# chipKIT_Max32.net
KiCad netlist of a schematic drawn in EAGLE
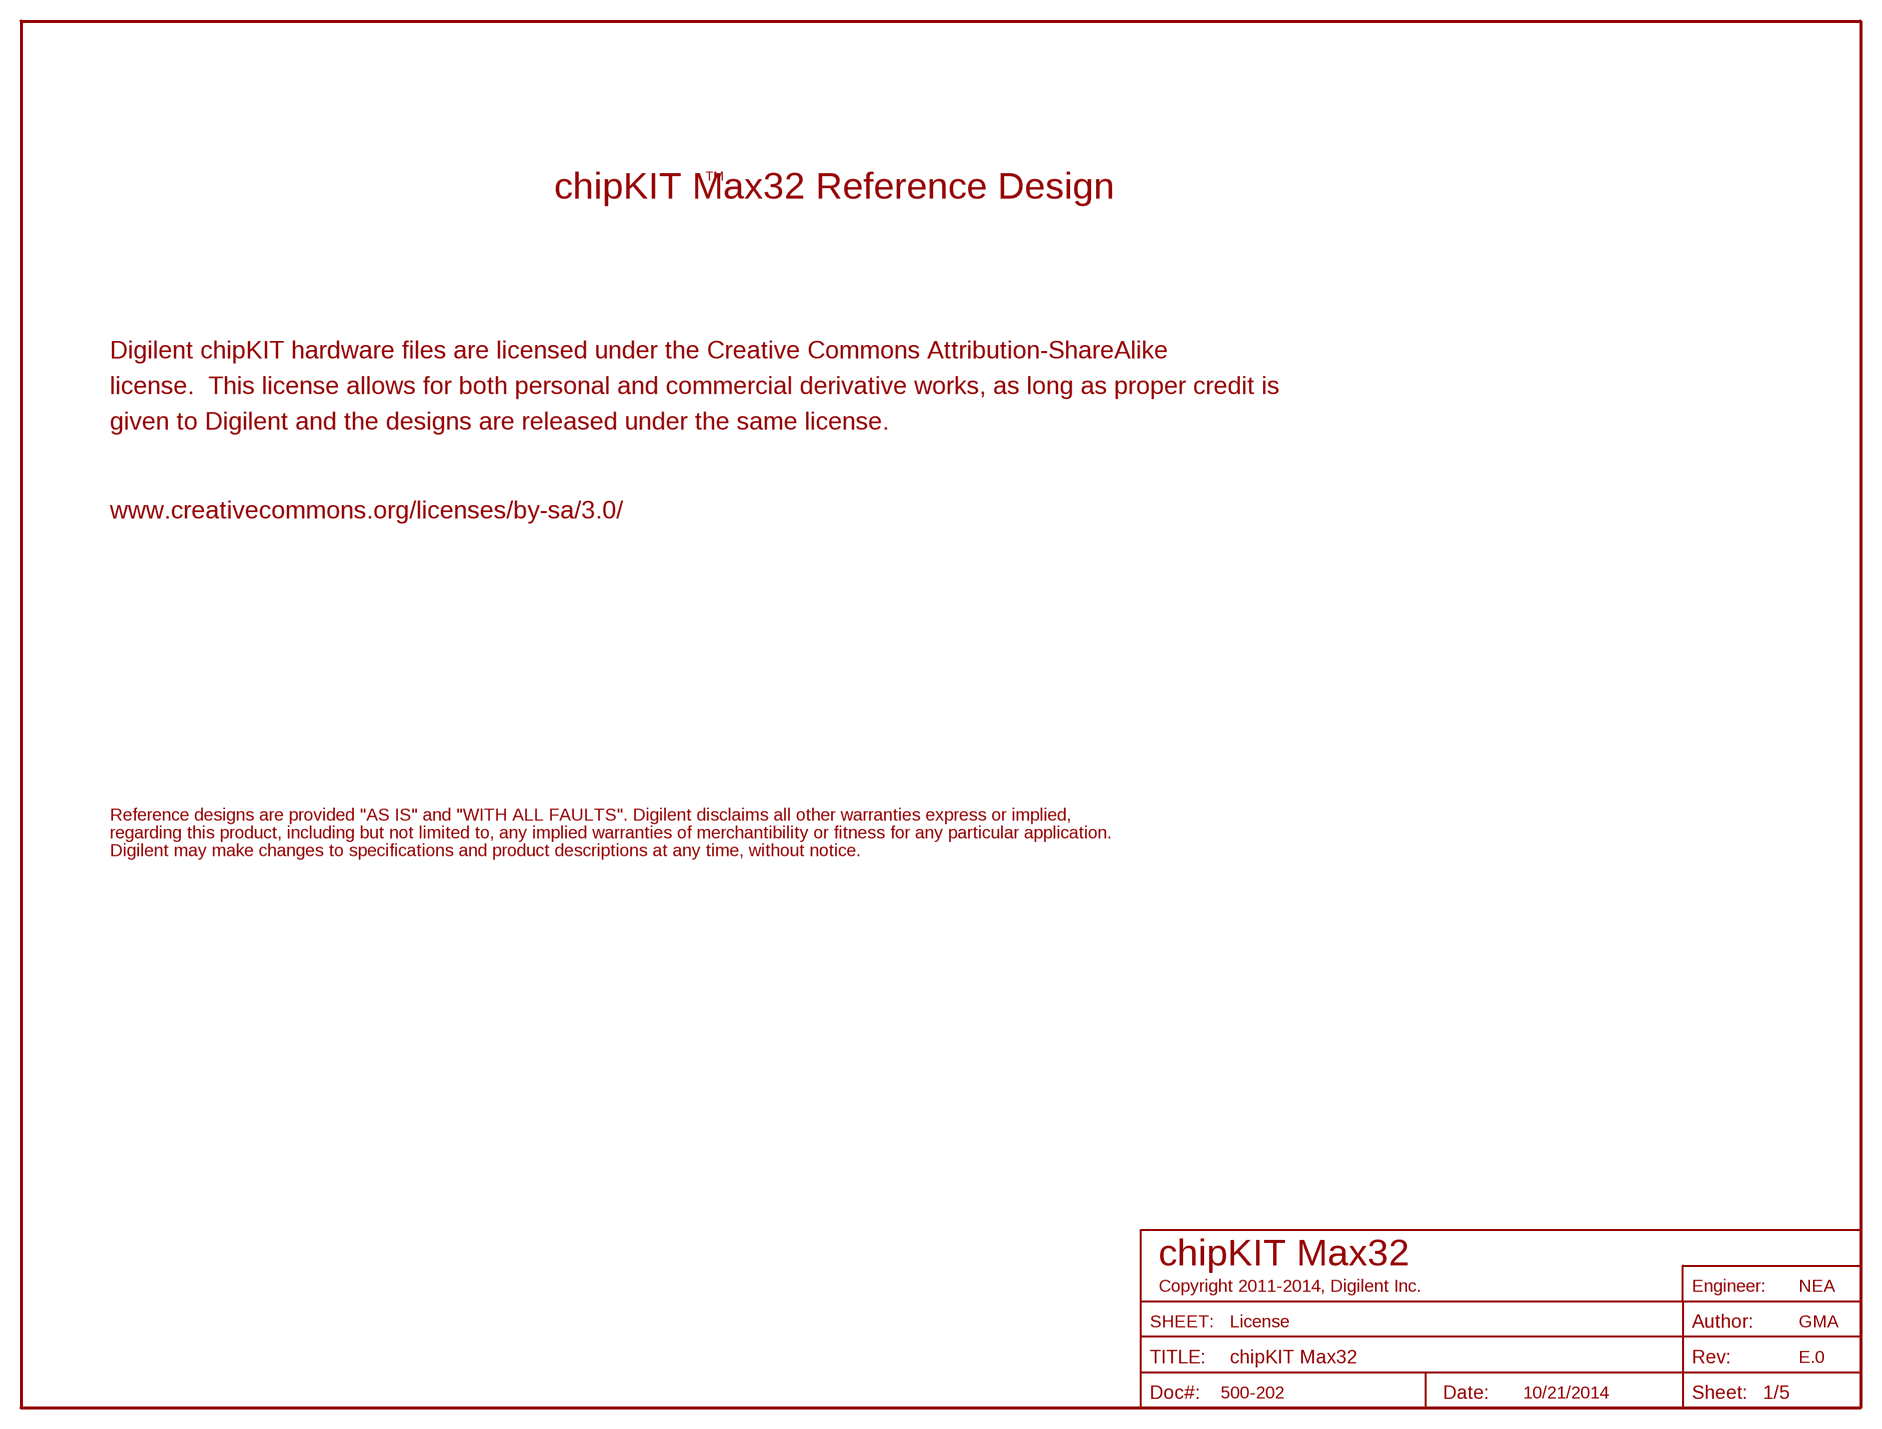
[diagram p0: schematic, sheet 1]
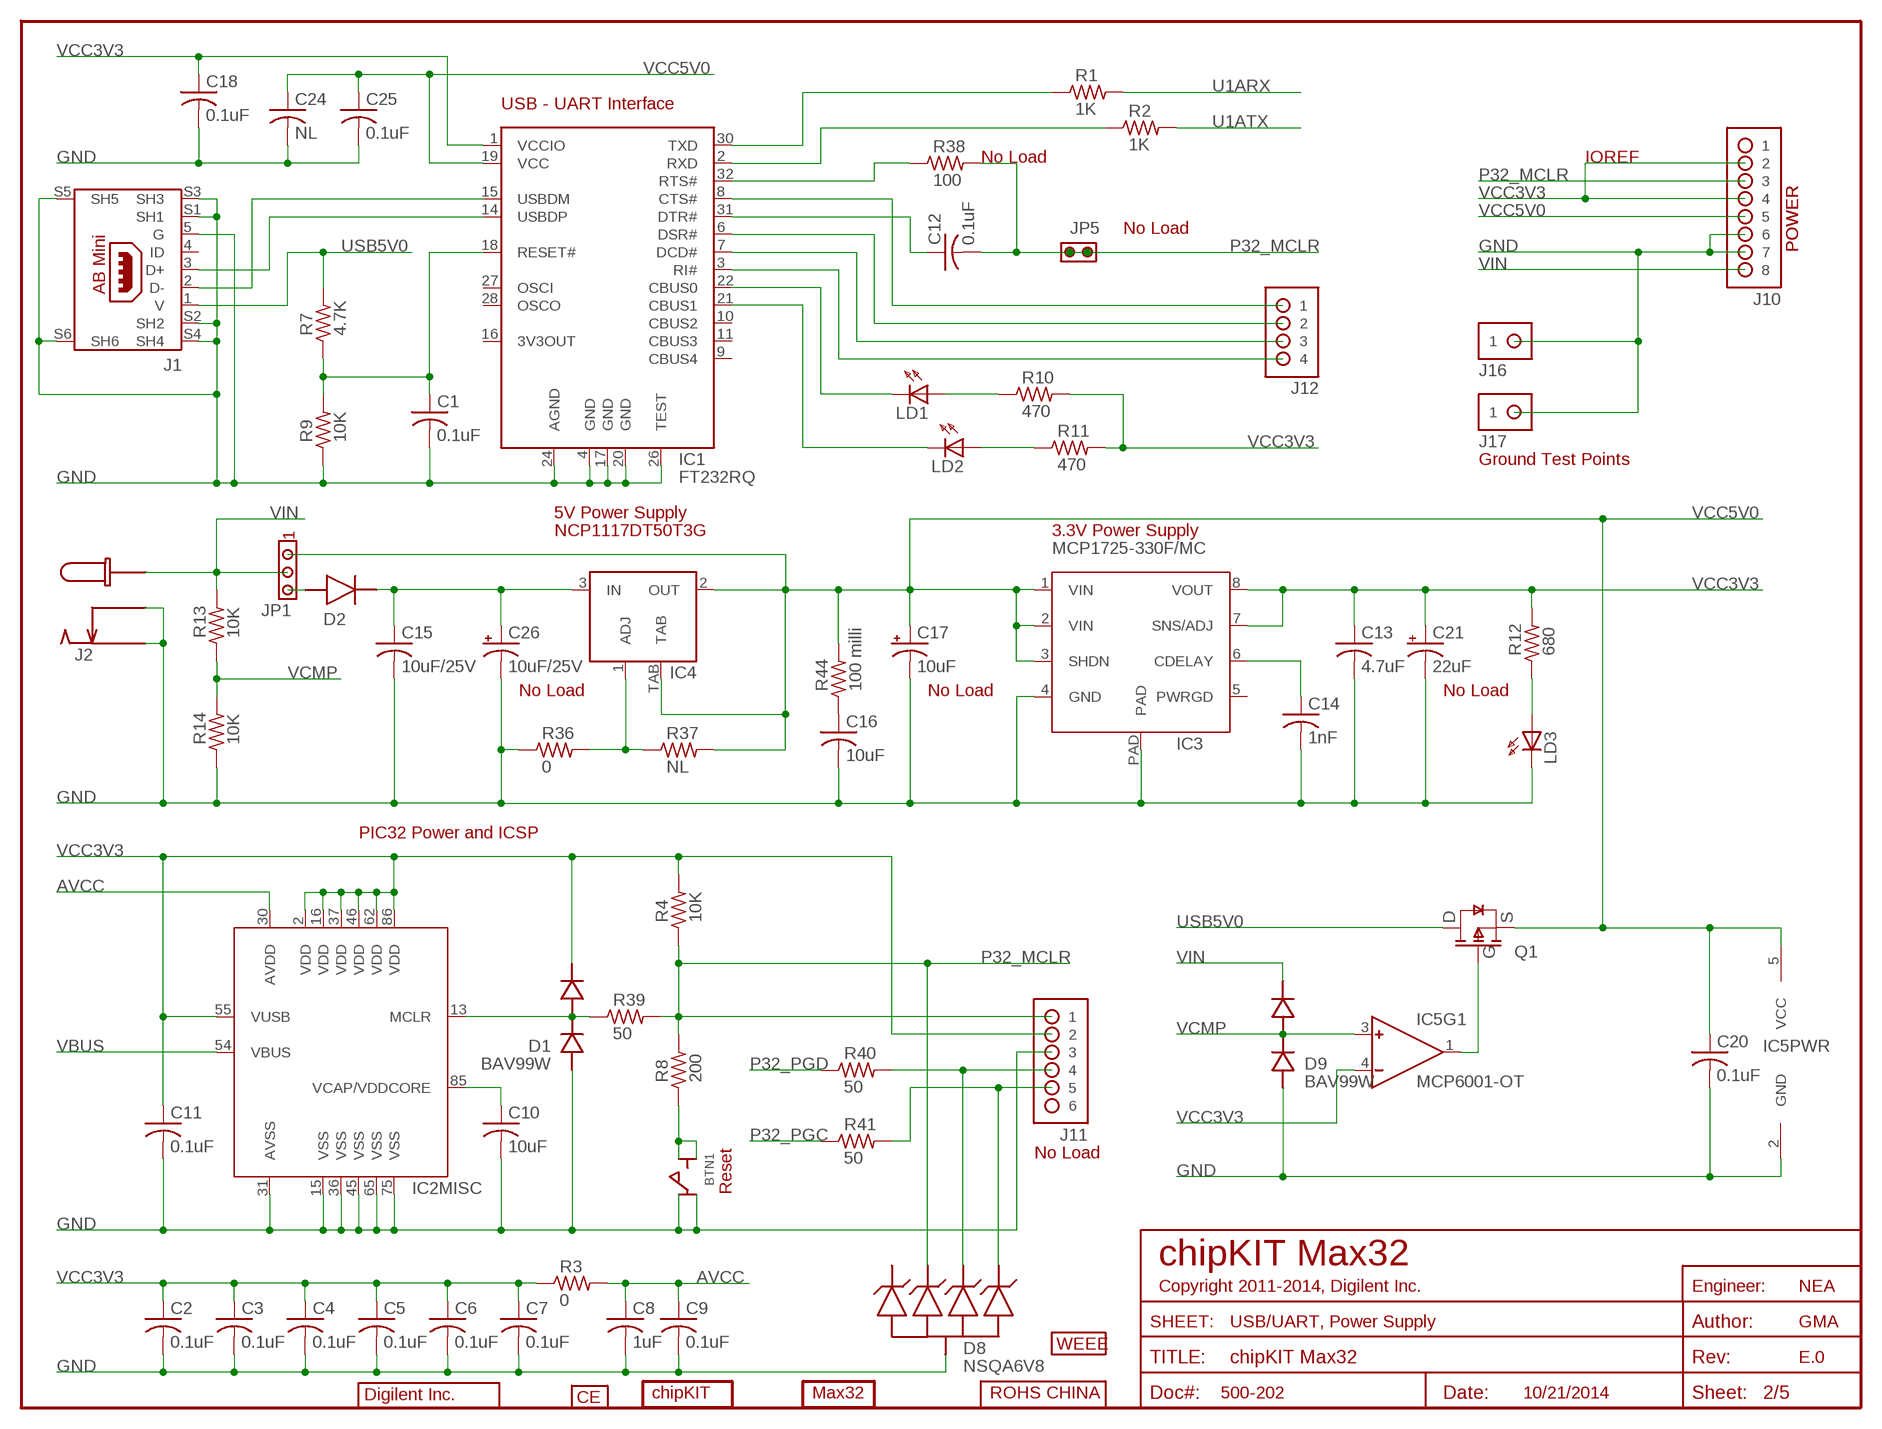
[diagram p1: schematic, sheet 2]
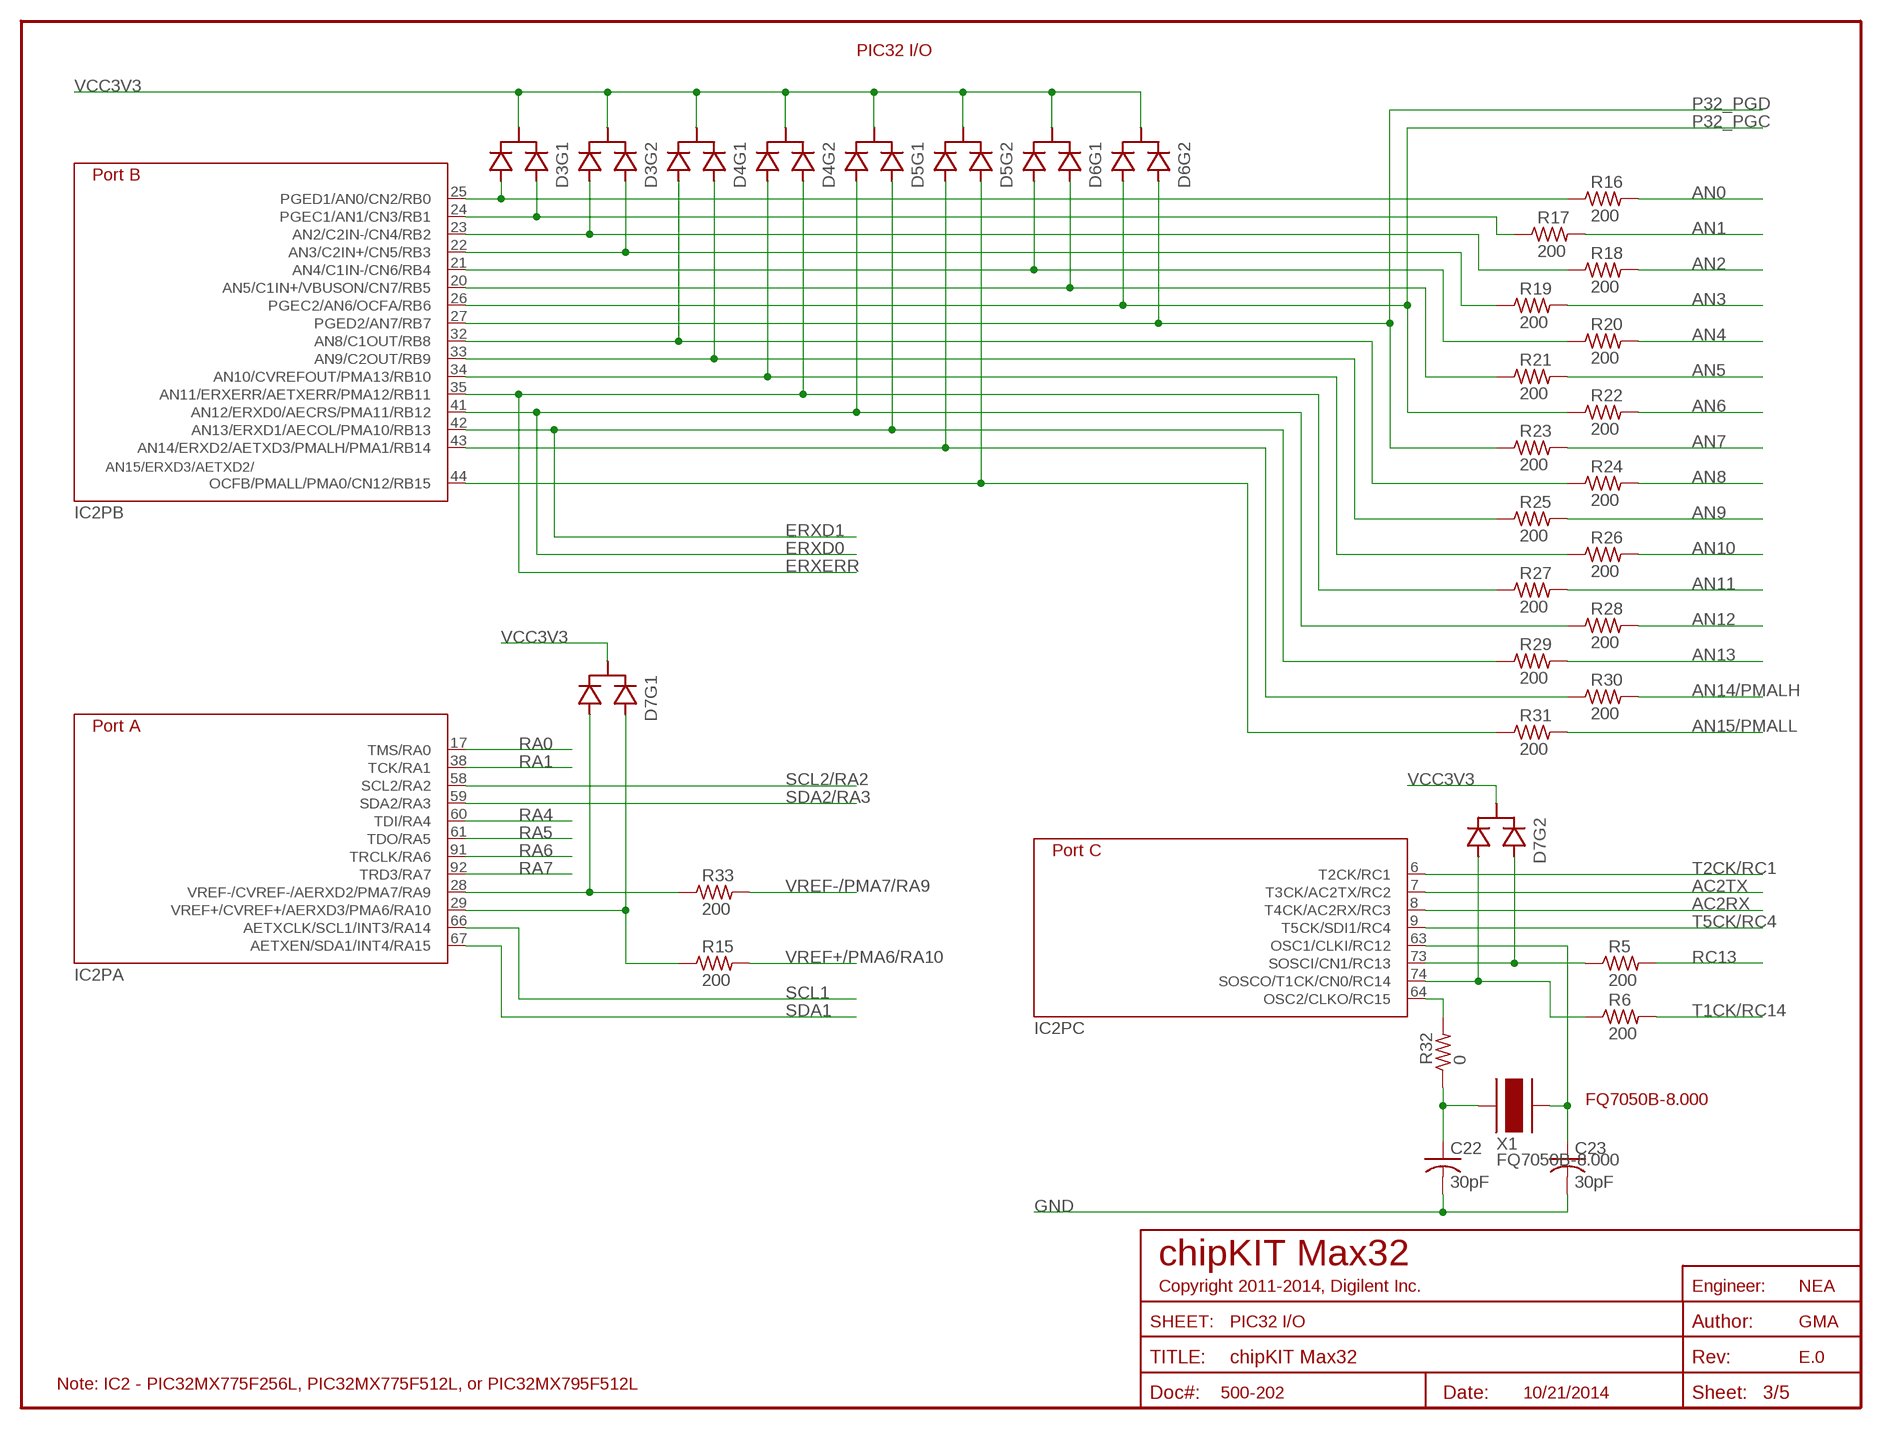
[diagram p2: schematic, sheet 3]
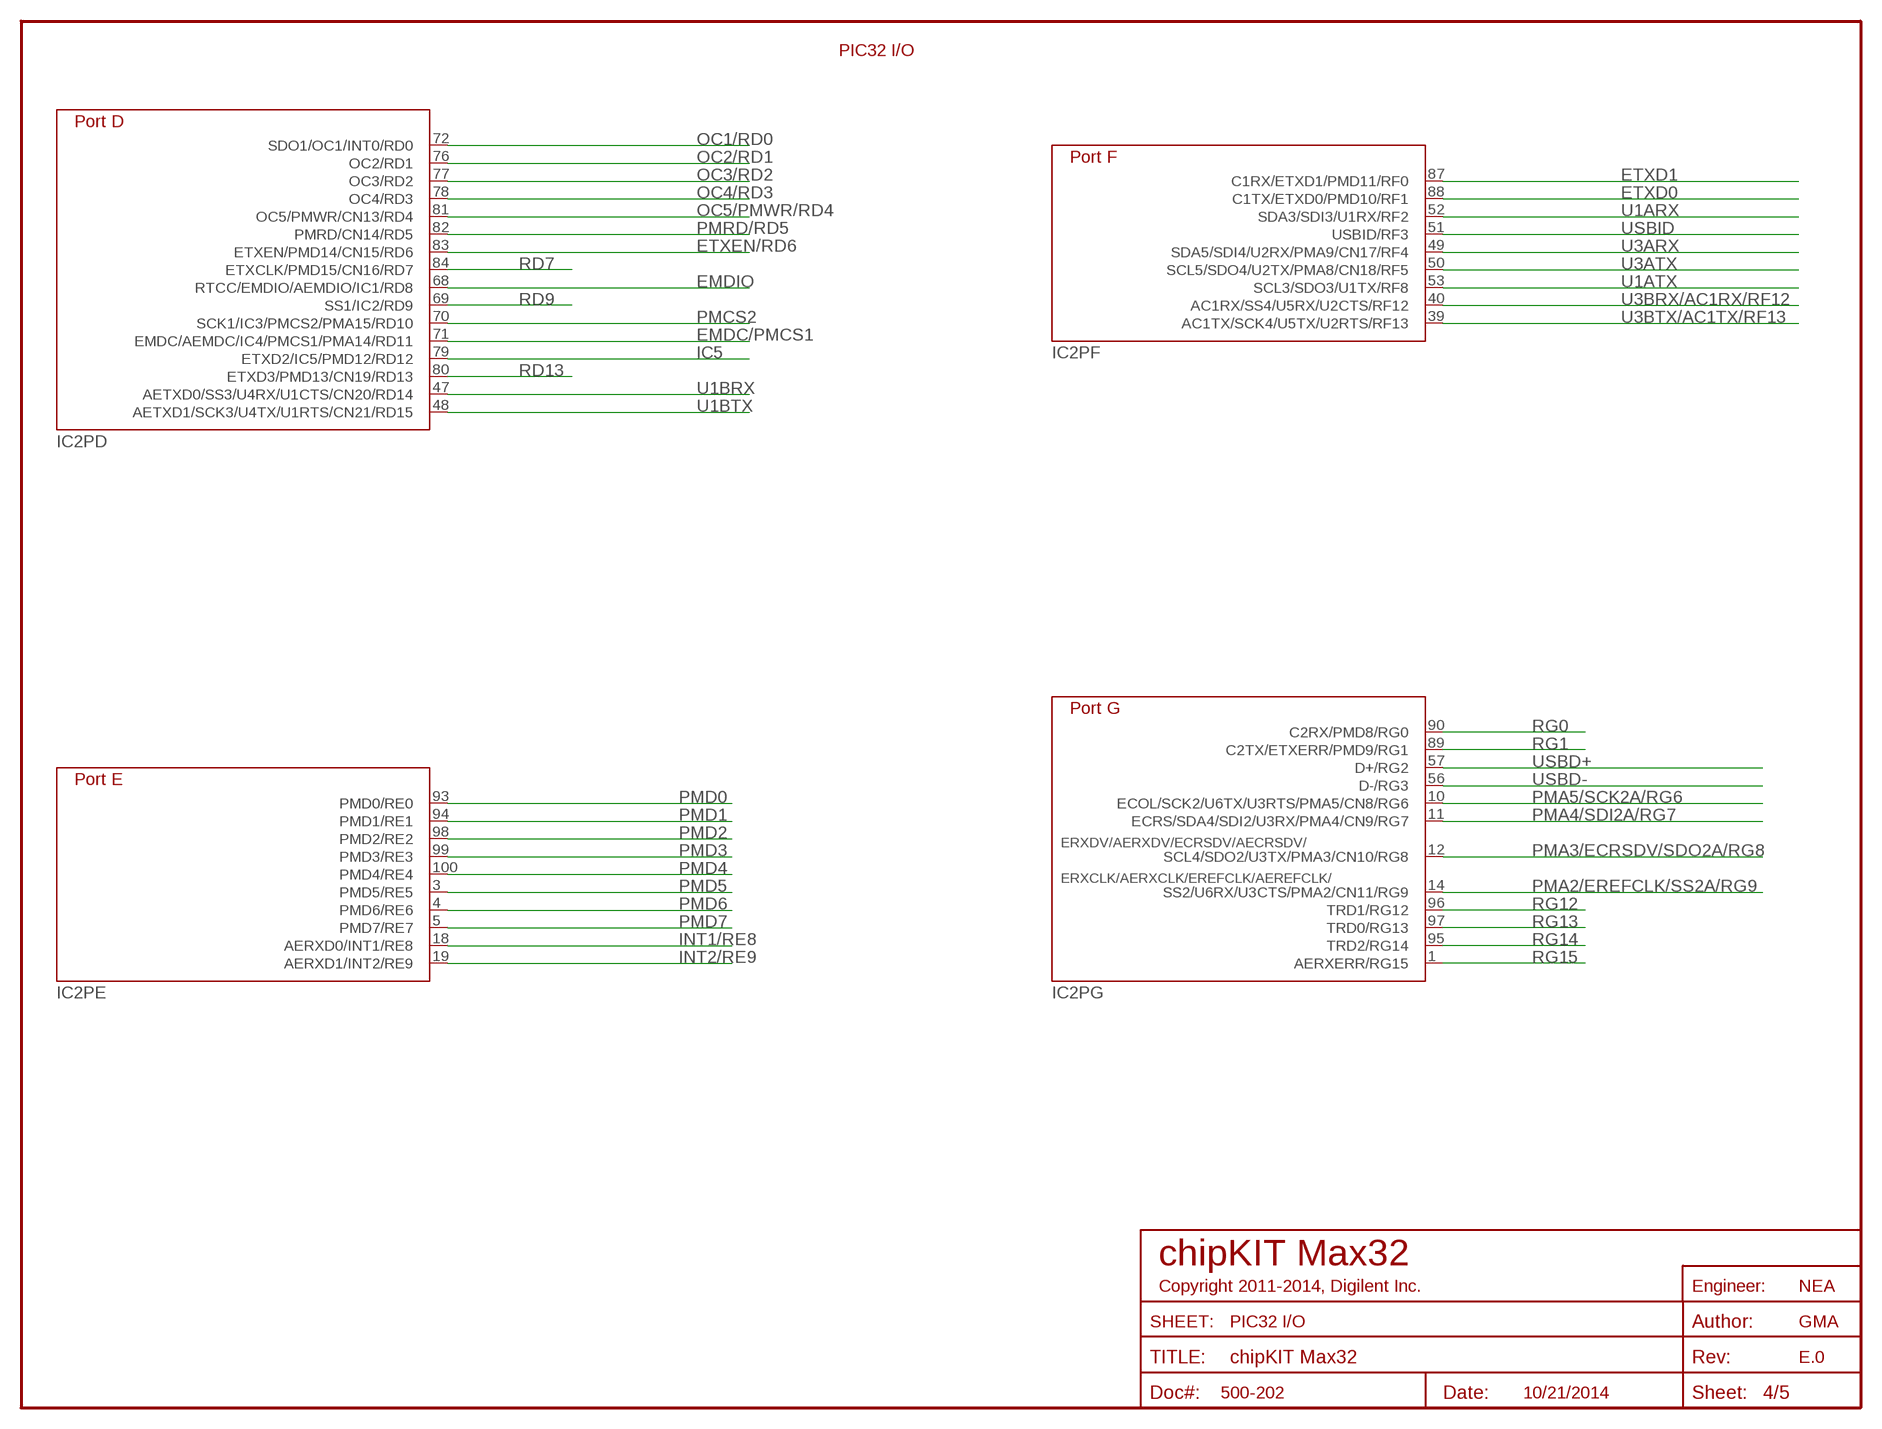
[diagram p3: schematic, sheet 4]
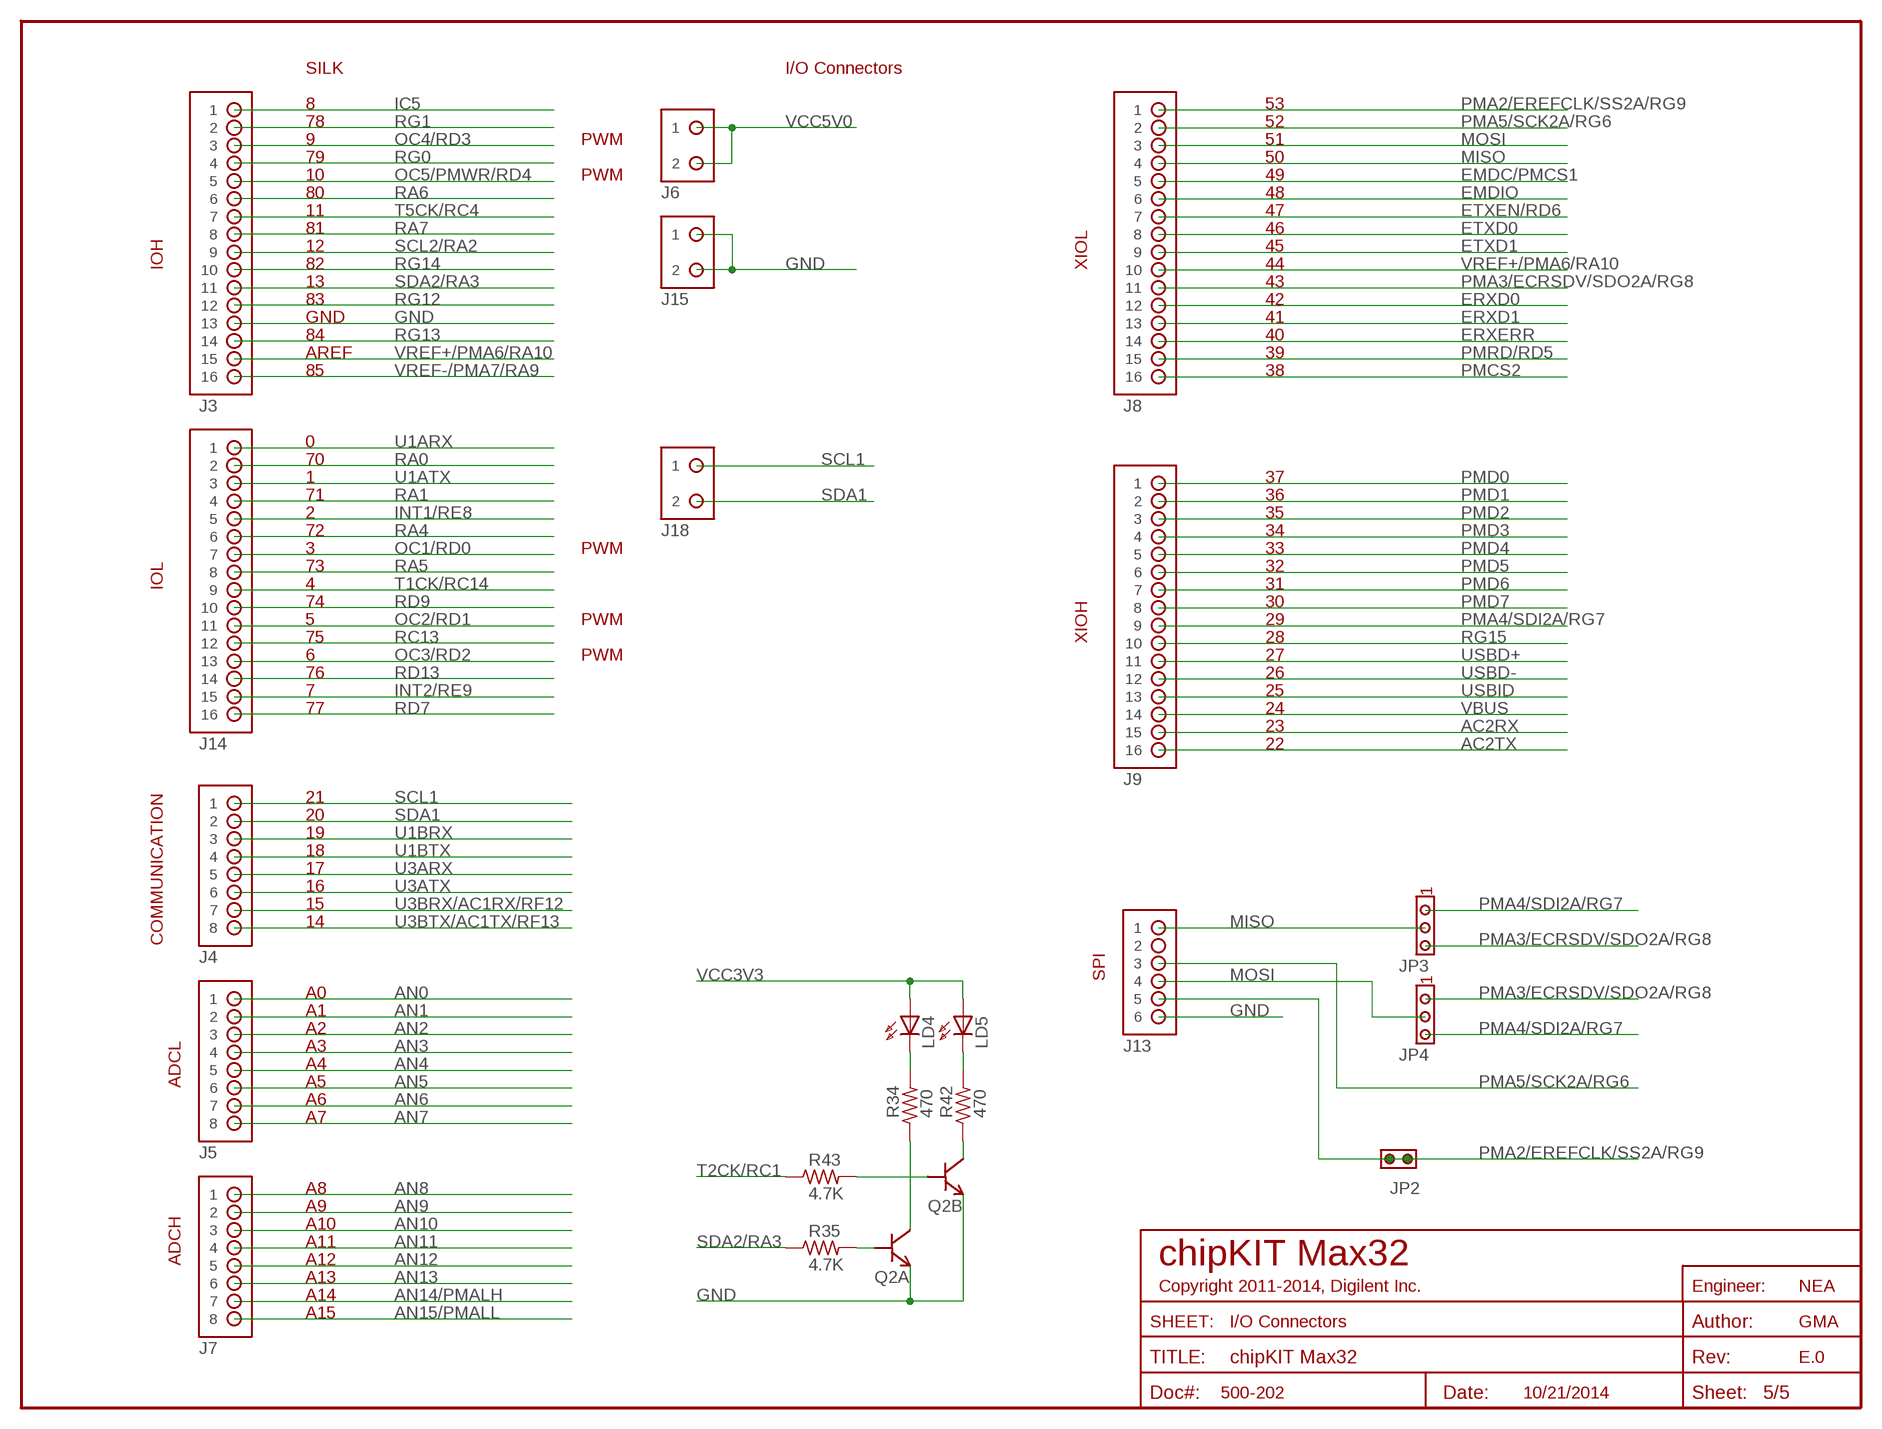
[diagram p4: schematic, sheet 5]

(export (version "E")
  (design (tool "Eeschema 10.0.6"))
  (components
    (comp (ref "BTN1")
      (value "SW-P8008")
      (footprint "eagle-import:SW-P8008")
      (libsource (lib "eagle-import") (part "SW-P8008"))
    )
    (comp (ref "C1")
      (value "0.1uF")
      (footprint "eagle-import:C0402S")
      (libsource (lib "eagle-import") (part "CAP-S0402S"))
    )
    (comp (ref "C2")
      (value "0.1uF")
      (footprint "eagle-import:C0402S")
      (libsource (lib "eagle-import") (part "CAP-S0402S"))
    )
    (comp (ref "C3")
      (value "0.1uF")
      (footprint "eagle-import:C0402S")
      (libsource (lib "eagle-import") (part "CAP-S0402S"))
    )
    (comp (ref "C4")
      (value "0.1uF")
      (footprint "eagle-import:C0402S")
      (libsource (lib "eagle-import") (part "CAP-S0402S"))
    )
    (comp (ref "C5")
      (value "0.1uF")
      (footprint "eagle-import:C0402S")
      (libsource (lib "eagle-import") (part "CAP-S0402S"))
    )
    (comp (ref "C6")
      (value "0.1uF")
      (footprint "eagle-import:C0402S")
      (libsource (lib "eagle-import") (part "CAP-S0402S"))
    )
    (comp (ref "C7")
      (value "0.1uF")
      (footprint "eagle-import:C0402S")
      (libsource (lib "eagle-import") (part "CAP-S0402S"))
    )
    (comp (ref "C8")
      (value "1uF")
      (footprint "eagle-import:C0402S")
      (libsource (lib "eagle-import") (part "CAP-S0402S"))
    )
    (comp (ref "C9")
      (value "0.1uF")
      (footprint "eagle-import:C0402S")
      (libsource (lib "eagle-import") (part "CAP-S0402S"))
    )
    (comp (ref "C10")
      (value "10uF")
      (footprint "eagle-import:C0603S")
      (libsource (lib "eagle-import") (part "CAP-S0603S"))
    )
    (comp (ref "C11")
      (value "0.1uF")
      (footprint "eagle-import:C0402S")
      (libsource (lib "eagle-import") (part "CAP-S0402S"))
    )
    (comp (ref "C12")
      (value "0.1uF")
      (footprint "eagle-import:C0402S")
      (libsource (lib "eagle-import") (part "CAP-S0402S"))
    )
    (comp (ref "C13")
      (value "4.7uF")
      (footprint "eagle-import:C0603S")
      (libsource (lib "eagle-import") (part "CAP-S0603S"))
    )
    (comp (ref "C14")
      (value "1nF")
      (footprint "eagle-import:C0402S")
      (libsource (lib "eagle-import") (part "CAP-S0402S"))
    )
    (comp (ref "C15")
      (value "10uF/25V")
      (footprint "eagle-import:C0805S")
      (libsource (lib "eagle-import") (part "CAP-S0805S"))
    )
    (comp (ref "C16")
      (value "10uF")
      (footprint "eagle-import:C0603S")
      (libsource (lib "eagle-import") (part "CAP-S0603S"))
    )
    (comp (ref "C17")
      (value "10uF")
      (footprint "eagle-import:CPOL3216")
      (libsource (lib "eagle-import") (part "CPOL-SA"))
    )
    (comp (ref "C18")
      (value "0.1uF")
      (footprint "eagle-import:C0402S")
      (libsource (lib "eagle-import") (part "CAP-S0402S"))
    )
    (comp (ref "C20")
      (value "0.1uF")
      (footprint "eagle-import:C0402")
      (libsource (lib "eagle-import") (part "CAP-S0402"))
    )
    (comp (ref "C21")
      (value "22uF")
      (footprint "eagle-import:CPOL3216")
      (libsource (lib "eagle-import") (part "CPOL-SA"))
    )
    (comp (ref "C24")
      (value "NL")
      (footprint "eagle-import:C0603S")
      (libsource (lib "eagle-import") (part "CAP-S0603S"))
    )
    (comp (ref "C25")
      (value "0.1uF")
      (footprint "eagle-import:C0402S")
      (libsource (lib "eagle-import") (part "CAP-S0402S"))
    )
    (comp (ref "C26")
      (value "10uF/25V")
      (footprint "eagle-import:CPOL3216")
      (libsource (lib "eagle-import") (part "CPOL-SA"))
    )
    (comp (ref "D1")
      (value "BAV99W")
      (footprint "eagle-import:SOT-323")
      (libsource (lib "eagle-import") (part "BAV99W"))
    )
    (comp (ref "D2")
      (value "B220A")
      (footprint "eagle-import:SMA")
      (libsource (lib "eagle-import") (part "DIODESMA"))
    )
    (comp (ref "D8")
      (value "NSQA6V8")
      (footprint "eagle-import:SOT-323-5")
      (libsource (lib "eagle-import") (part "NSQA6V8"))
    )
    (comp (ref "D9")
      (value "BAV99W")
      (footprint "eagle-import:SOT-323")
      (libsource (lib "eagle-import") (part "BAV99W"))
    )
    (comp (ref "IC1")
      (value "FT232RQ")
      (footprint "eagle-import:QFN32")
      (libsource (lib "eagle-import") (part "FT232RQ"))
    )
    (comp (ref "IC2")
      (value "PIC32MX7X5FL-PT")
      (footprint "eagle-import:TQ100-PT")
      (libsource (lib "eagle-import") (part "PIC32MX7X5FL-PT"))
    )
    (comp (ref "IC3")
      (value "MCP1725-330F/MC")
      (footprint "eagle-import:DFN8-MC")
      (libsource (lib "eagle-import") (part "MCP1725MC"))
    )
    (comp (ref "IC4")
      (value "NCP1117DT50T3G")
      (footprint "eagle-import:SOT223")
      (libsource (lib "eagle-import") (part "LM1117MP"))
    )
    (comp (ref "IC5")
      (value "MCP6001-OT")
      (footprint "eagle-import:SOT23-5-OT")
      (libsource (lib "eagle-import") (part "MCP6001-OT"))
    )
    (comp (ref "J1")
      (value "USB-AB-MINI")
      (footprint "eagle-import:USB-AB-MINI")
      (libsource (lib "eagle-import") (part "USB-AB-MINI"))
    )
    (comp (ref "J2")
      (value "CON-COAX-KLD0202-S")
      (footprint "eagle-import:KLD-0202S")
      (libsource (lib "eagle-import") (part "CON-COAX-KLD0202-S"))
    )
    (comp (ref "J10")
      (value "ST Female")
      (footprint "eagle-import:HDR-1X8")
      (libsource (lib "eagle-import") (part "HDR-1X8"))
    )
    (comp (ref "J11")
      (value "No Load")
      (footprint "eagle-import:HDR-1X6_OFFSET")
      (libsource (lib "eagle-import") (part "HDR-1X6-OFFSET"))
    )
    (comp (ref "J12")
      (value "HDR-1X4")
      (footprint "eagle-import:HDR-1X4")
      (libsource (lib "eagle-import") (part "HDR-1X4"))
    )
    (comp (ref "J16")
      (value "HDR-1X1")
      (footprint "eagle-import:HDR-1X1")
      (libsource (lib "eagle-import") (part "HDR-1X1"))
    )
    (comp (ref "J17")
      (value "HDR-1X1")
      (footprint "eagle-import:HDR-1X1")
      (libsource (lib "eagle-import") (part "HDR-1X1"))
    )
    (comp (ref "JP1")
      (value "JPR-1X3")
      (footprint "eagle-import:JPR-1X3")
      (libsource (lib "eagle-import") (part "JPR-1X3"))
    )
    (comp (ref "JP5")
      (value "No Load")
      (footprint "eagle-import:JPR-1X2")
      (libsource (lib "eagle-import") (part "JPR-1X2"))
    )
    (comp (ref "LD1")
      (value "LED-S0603-RED")
      (footprint "eagle-import:D0603")
      (libsource (lib "eagle-import") (part "LED-S0603"))
    )
    (comp (ref "LD2")
      (value "LED-S0603-RED")
      (footprint "eagle-import:D0603")
      (libsource (lib "eagle-import") (part "LED-S0603"))
    )
    (comp (ref "LD3")
      (value "LED-S0603-RED")
      (footprint "eagle-import:D0603")
      (libsource (lib "eagle-import") (part "LED-S0603"))
    )
    (comp (ref "LOGO1")
      (value "ROHS-CHINA-INV")
      (footprint "eagle-import:ROHS_CHINA_INV_LOGO")
      (libsource (lib "eagle-import") (part "ROHS-CHINA-INV"))
    )
    (comp (ref "LOGO2")
      (value "WEEE-L")
      (footprint "eagle-import:WEEE_LOGO2")
      (libsource (lib "eagle-import") (part "WEEE-L"))
    )
    (comp (ref "LOGO4")
      (value "MAX32_LOGO")
      (footprint "eagle-import:MAX32_LOGO")
      (libsource (lib "eagle-import") (part "MAX32_LOGO"))
    )
    (comp (ref "LOGO5")
      (value "CHIPKIT")
      (footprint "eagle-import:CHIPKIT_LOGO")
      (libsource (lib "eagle-import") (part "CHIPKIT"))
    )
    (comp (ref "LOGO6")
      (value "CE")
      (footprint "eagle-import:CE_LOGO")
      (libsource (lib "eagle-import") (part "CE"))
    )
    (comp (ref "LOGO7")
      (value "DIGILENT_INC-BT-1500")
      (footprint "eagle-import:DIGILENT_BEYOND_1500_LOGO")
      (libsource (lib "eagle-import") (part "DIGILENT_INC-BT-1500"))
    )
    (comp (ref "Q1")
      (value "FDN340P")
      (footprint "eagle-import:SOT23")
      (libsource (lib "eagle-import") (part "FDN340P"))
    )
    (comp (ref "R1")
      (value "1K")
      (footprint "eagle-import:R0402S")
      (libsource (lib "eagle-import") (part "RES-S0402S"))
    )
    (comp (ref "R2")
      (value "1K")
      (footprint "eagle-import:R0402S")
      (libsource (lib "eagle-import") (part "RES-S0402S"))
    )
    (comp (ref "R3")
      (value "0")
      (footprint "eagle-import:R0603")
      (libsource (lib "eagle-import") (part "RES-S0603"))
    )
    (comp (ref "R4")
      (value "10K")
      (footprint "eagle-import:R0402S")
      (libsource (lib "eagle-import") (part "RES-S0402S"))
    )
    (comp (ref "R7")
      (value "4.7K")
      (footprint "eagle-import:R0402S")
      (libsource (lib "eagle-import") (part "RES-S0402S"))
    )
    (comp (ref "R8")
      (value "200")
      (footprint "eagle-import:R0402S")
      (libsource (lib "eagle-import") (part "RES-S0402S"))
    )
    (comp (ref "R9")
      (value "10K")
      (footprint "eagle-import:R0402S")
      (libsource (lib "eagle-import") (part "RES-S0402S"))
    )
    (comp (ref "R10")
      (value "470")
      (footprint "eagle-import:R0402S")
      (libsource (lib "eagle-import") (part "RES-S0402S"))
    )
    (comp (ref "R11")
      (value "470")
      (footprint "eagle-import:R0402S")
      (libsource (lib "eagle-import") (part "RES-S0402S"))
    )
    (comp (ref "R12")
      (value "680")
      (footprint "eagle-import:R0402S")
      (libsource (lib "eagle-import") (part "RES-S0402S"))
    )
    (comp (ref "R13")
      (value "10K")
      (footprint "eagle-import:R0402S")
      (libsource (lib "eagle-import") (part "RES-S0402S"))
    )
    (comp (ref "R14")
      (value "10K")
      (footprint "eagle-import:R0402S")
      (libsource (lib "eagle-import") (part "RES-S0402S"))
    )
    (comp (ref "R36")
      (value "0")
      (footprint "eagle-import:R0402S")
      (libsource (lib "eagle-import") (part "RES-S0402S"))
    )
    (comp (ref "R37")
      (value "NL")
      (footprint "eagle-import:R0402S")
      (libsource (lib "eagle-import") (part "RES-S0402S"))
    )
    (comp (ref "R38")
      (value "100")
      (footprint "eagle-import:R0402S")
      (libsource (lib "eagle-import") (part "RES-S0402S"))
    )
    (comp (ref "R39")
      (value "50")
      (footprint "eagle-import:R0402S")
      (libsource (lib "eagle-import") (part "RES-S0402S"))
    )
    (comp (ref "R40")
      (value "50")
      (footprint "eagle-import:R0402S")
      (libsource (lib "eagle-import") (part "RES-S0402S"))
    )
    (comp (ref "R41")
      (value "50")
      (footprint "eagle-import:R0402S")
      (libsource (lib "eagle-import") (part "RES-S0402S"))
    )
    (comp (ref "R44")
      (value "100 milli")
      (footprint "eagle-import:R0603S")
      (libsource (lib "eagle-import") (part "RES-S0603S"))
    )
    (comp (ref "J3")
      (value "HDR-2X8")
      (footprint "eagle-import:HDR-2X8")
      (libsource (lib "eagle-import") (part "HDR-2X8"))
    )
    (comp (ref "J4")
      (value "HDR-1X8")
      (footprint "eagle-import:HDR-1X8")
      (libsource (lib "eagle-import") (part "HDR-1X8"))
    )
    (comp (ref "J5")
      (value "HDR-1X8")
      (footprint "eagle-import:HDR-1X8")
      (libsource (lib "eagle-import") (part "HDR-1X8"))
    )
    (comp (ref "J6")
      (value "HDR-1X2")
      (footprint "eagle-import:HDR-1X2")
      (libsource (lib "eagle-import") (part "HDR-1X2"))
    )
    (comp (ref "J7")
      (value "HDR-1X8")
      (footprint "eagle-import:HDR-1X8")
      (libsource (lib "eagle-import") (part "HDR-1X8"))
    )
    (comp (ref "J8")
      (value "HDR-2X8")
      (footprint "eagle-import:HDR-2X8")
      (libsource (lib "eagle-import") (part "HDR-2X8"))
    )
    (comp (ref "J9")
      (value "HDR-2X8")
      (footprint "eagle-import:HDR-2X8")
      (libsource (lib "eagle-import") (part "HDR-2X8"))
    )
    (comp (ref "J13")
      (value "HDR-2X3")
      (footprint "eagle-import:HDR-2X3")
      (libsource (lib "eagle-import") (part "HDR-2X3"))
    )
    (comp (ref "J14")
      (value "HDR-2X8")
      (footprint "eagle-import:HDR-2X8")
      (libsource (lib "eagle-import") (part "HDR-2X8"))
    )
    (comp (ref "J15")
      (value "HDR-1X2")
      (footprint "eagle-import:HDR-1X2")
      (libsource (lib "eagle-import") (part "HDR-1X2"))
    )
    (comp (ref "J18")
      (value "ST FEMALE")
      (footprint "eagle-import:HDR-1X2")
      (libsource (lib "eagle-import") (part "HDR-1X2"))
    )
    (comp (ref "JP2")
      (value "JPR-1X2")
      (footprint "eagle-import:JPR-1X2")
      (libsource (lib "eagle-import") (part "JPR-1X2"))
    )
    (comp (ref "JP3")
      (value "JPR-1X3")
      (footprint "eagle-import:JPR-1X3")
      (libsource (lib "eagle-import") (part "JPR-1X3"))
    )
    (comp (ref "JP4")
      (value "JPR-1X3")
      (footprint "eagle-import:JPR-1X3")
      (libsource (lib "eagle-import") (part "JPR-1X3"))
    )
    (comp (ref "LD4")
      (value "LED-S0603-GRN")
      (footprint "eagle-import:D0603")
      (libsource (lib "eagle-import") (part "LED-S0603"))
    )
    (comp (ref "LD5")
      (value "LED-S0603")
      (footprint "eagle-import:D0603")
      (libsource (lib "eagle-import") (part "LED-S0603"))
    )
    (comp (ref "Q2")
      (value "MBT3904DW1T1")
      (footprint "eagle-import:SOT-363")
      (libsource (lib "eagle-import") (part "MBT3904DW1T1"))
    )
    (comp (ref "R34")
      (value "470")
      (footprint "eagle-import:R0402S")
      (libsource (lib "eagle-import") (part "RES-S0402S"))
    )
    (comp (ref "R35")
      (value "4.7K")
      (footprint "eagle-import:R0402S")
      (libsource (lib "eagle-import") (part "RES-S0402S"))
    )
    (comp (ref "R42")
      (value "470")
      (footprint "eagle-import:R0402S")
      (libsource (lib "eagle-import") (part "RES-S0402S"))
    )
    (comp (ref "R43")
      (value "4.7K")
      (footprint "eagle-import:R0402S")
      (libsource (lib "eagle-import") (part "RES-S0402S"))
    )
    (comp (ref "C22")
      (value "30pF")
      (footprint "eagle-import:C0402S")
      (libsource (lib "eagle-import") (part "CAP-S0402S"))
    )
    (comp (ref "C23")
      (value "30pF")
      (footprint "eagle-import:C0402S")
      (libsource (lib "eagle-import") (part "CAP-S0402S"))
    )
    (comp (ref "D3")
      (value "BAV70S")
      (footprint "eagle-import:SOT-363")
      (libsource (lib "eagle-import") (part "BAV70S"))
    )
    (comp (ref "D4")
      (value "BAV70S")
      (footprint "eagle-import:SOT-363")
      (libsource (lib "eagle-import") (part "BAV70S"))
    )
    (comp (ref "D5")
      (value "BAV70S")
      (footprint "eagle-import:SOT-363")
      (libsource (lib "eagle-import") (part "BAV70S"))
    )
    (comp (ref "D6")
      (value "BAV70S")
      (footprint "eagle-import:SOT-363")
      (libsource (lib "eagle-import") (part "BAV70S"))
    )
    (comp (ref "D7")
      (value "BAV70S")
      (footprint "eagle-import:SOT-363")
      (libsource (lib "eagle-import") (part "BAV70S"))
    )
    (comp (ref "R5")
      (value "200")
      (footprint "eagle-import:R0402S")
      (libsource (lib "eagle-import") (part "RES-S0402S"))
    )
    (comp (ref "R6")
      (value "200")
      (footprint "eagle-import:R0402S")
      (libsource (lib "eagle-import") (part "RES-S0402S"))
    )
    (comp (ref "R15")
      (value "200")
      (footprint "eagle-import:R0402S")
      (libsource (lib "eagle-import") (part "RES-S0402S"))
    )
    (comp (ref "R16")
      (value "200")
      (footprint "eagle-import:R0402S")
      (libsource (lib "eagle-import") (part "RES-S0402S"))
    )
    (comp (ref "R17")
      (value "200")
      (footprint "eagle-import:R0402S")
      (libsource (lib "eagle-import") (part "RES-S0402S"))
    )
    (comp (ref "R18")
      (value "200")
      (footprint "eagle-import:R0402S")
      (libsource (lib "eagle-import") (part "RES-S0402S"))
    )
    (comp (ref "R19")
      (value "200")
      (footprint "eagle-import:R0402S")
      (libsource (lib "eagle-import") (part "RES-S0402S"))
    )
    (comp (ref "R20")
      (value "200")
      (footprint "eagle-import:R0402S")
      (libsource (lib "eagle-import") (part "RES-S0402S"))
    )
    (comp (ref "R21")
      (value "200")
      (footprint "eagle-import:R0402S")
      (libsource (lib "eagle-import") (part "RES-S0402S"))
    )
    (comp (ref "R22")
      (value "200")
      (footprint "eagle-import:R0402S")
      (libsource (lib "eagle-import") (part "RES-S0402S"))
    )
    (comp (ref "R23")
      (value "200")
      (footprint "eagle-import:R0402S")
      (libsource (lib "eagle-import") (part "RES-S0402S"))
    )
    (comp (ref "R24")
      (value "200")
      (footprint "eagle-import:R0402S")
      (libsource (lib "eagle-import") (part "RES-S0402S"))
    )
    (comp (ref "R25")
      (value "200")
      (footprint "eagle-import:R0402S")
      (libsource (lib "eagle-import") (part "RES-S0402S"))
    )
    (comp (ref "R26")
      (value "200")
      (footprint "eagle-import:R0402S")
      (libsource (lib "eagle-import") (part "RES-S0402S"))
    )
    (comp (ref "R27")
      (value "200")
      (footprint "eagle-import:R0402S")
      (libsource (lib "eagle-import") (part "RES-S0402S"))
    )
    (comp (ref "R28")
      (value "200")
      (footprint "eagle-import:R0402S")
      (libsource (lib "eagle-import") (part "RES-S0402S"))
    )
    (comp (ref "R29")
      (value "200")
      (footprint "eagle-import:R0402S")
      (libsource (lib "eagle-import") (part "RES-S0402S"))
    )
    (comp (ref "R30")
      (value "200")
      (footprint "eagle-import:R0402S")
      (libsource (lib "eagle-import") (part "RES-S0402S"))
    )
    (comp (ref "R31")
      (value "200")
      (footprint "eagle-import:R0402S")
      (libsource (lib "eagle-import") (part "RES-S0402S"))
    )
    (comp (ref "R32")
      (value "0")
      (footprint "eagle-import:R0402S")
      (libsource (lib "eagle-import") (part "RES-S0402S"))
    )
    (comp (ref "R33")
      (value "200")
      (footprint "eagle-import:R0402S")
      (libsource (lib "eagle-import") (part "RES-S0402S"))
    )
    (comp (ref "X1")
      (value "FQ7050B-8.000")
      (footprint "eagle-import:FQ7050B")
      (libsource (lib "eagle-import") (part "XTAL-FQ7050B"))
    )
  )
  (nets
    (net (code "1") (name "AC2RX") (class "Default")
      (node (ref "IC2") (pin "8") (pinfunction "T4CK/AC2RX/RC3_8") (pintype "bidirectional"))
      (node (ref "J9") (pin "15") (pinfunction "15_15") (pintype "passive"))
    )
    (net (code "2") (name "AC2TX") (class "Default")
      (node (ref "IC2") (pin "7") (pinfunction "T3CK/AC2TX/RC2_7") (pintype "bidirectional"))
      (node (ref "J9") (pin "16") (pinfunction "16_16") (pintype "passive"))
    )
    (net (code "3") (name "AN0") (class "Default")
      (node (ref "J5") (pin "1") (pinfunction "1_1") (pintype "passive"))
      (node (ref "R16") (pin "2") (pinfunction "2_2") (pintype "passive"))
    )
    (net (code "4") (name "AN1") (class "Default")
      (node (ref "J5") (pin "2") (pinfunction "2_2") (pintype "passive"))
      (node (ref "R17") (pin "2") (pinfunction "2_2") (pintype "passive"))
    )
    (net (code "5") (name "AN2") (class "Default")
      (node (ref "J5") (pin "3") (pinfunction "3_3") (pintype "passive"))
      (node (ref "R18") (pin "2") (pinfunction "2_2") (pintype "passive"))
    )
    (net (code "6") (name "AN3") (class "Default")
      (node (ref "J5") (pin "4") (pinfunction "4_4") (pintype "passive"))
      (node (ref "R19") (pin "2") (pinfunction "2_2") (pintype "passive"))
    )
    (net (code "7") (name "AN4") (class "Default")
      (node (ref "J5") (pin "5") (pinfunction "5_5") (pintype "passive"))
      (node (ref "R20") (pin "2") (pinfunction "2_2") (pintype "passive"))
    )
    (net (code "8") (name "AN5") (class "Default")
      (node (ref "J5") (pin "6") (pinfunction "6_6") (pintype "passive"))
      (node (ref "R21") (pin "2") (pinfunction "2_2") (pintype "passive"))
    )
    (net (code "9") (name "AN6") (class "Default")
      (node (ref "J5") (pin "7") (pinfunction "7_7") (pintype "passive"))
      (node (ref "R22") (pin "2") (pinfunction "2_2") (pintype "passive"))
    )
    (net (code "10") (name "AN7") (class "Default")
      (node (ref "J5") (pin "8") (pinfunction "8_8") (pintype "passive"))
      (node (ref "R23") (pin "2") (pinfunction "2_2") (pintype "passive"))
    )
    (net (code "11") (name "AN8") (class "Default")
      (node (ref "J7") (pin "1") (pinfunction "1_1") (pintype "passive"))
      (node (ref "R24") (pin "2") (pinfunction "2_2") (pintype "passive"))
    )
    (net (code "12") (name "AN9") (class "Default")
      (node (ref "J7") (pin "2") (pinfunction "2_2") (pintype "passive"))
      (node (ref "R25") (pin "2") (pinfunction "2_2") (pintype "passive"))
    )
    (net (code "13") (name "AN10") (class "Default")
      (node (ref "J7") (pin "3") (pinfunction "3_3") (pintype "passive"))
      (node (ref "R26") (pin "2") (pinfunction "2_2") (pintype "passive"))
    )
    (net (code "14") (name "AN11") (class "Default")
      (node (ref "J7") (pin "4") (pinfunction "4_4") (pintype "passive"))
      (node (ref "R27") (pin "2") (pinfunction "2_2") (pintype "passive"))
    )
    (net (code "15") (name "AN12") (class "Default")
      (node (ref "J7") (pin "5") (pinfunction "5_5") (pintype "passive"))
      (node (ref "R28") (pin "2") (pinfunction "2_2") (pintype "passive"))
    )
    (net (code "16") (name "AN13") (class "Default")
      (node (ref "J7") (pin "6") (pinfunction "6_6") (pintype "passive"))
      (node (ref "R29") (pin "2") (pinfunction "2_2") (pintype "passive"))
    )
    (net (code "17") (name "AN14{slash}PMALH") (class "Default")
      (node (ref "J7") (pin "7") (pinfunction "7_7") (pintype "passive"))
      (node (ref "R30") (pin "2") (pinfunction "2_2") (pintype "passive"))
    )
    (net (code "18") (name "AN15{slash}PMALL") (class "Default")
      (node (ref "J7") (pin "8") (pinfunction "8_8") (pintype "passive"))
      (node (ref "R31") (pin "2") (pinfunction "2_2") (pintype "passive"))
    )
    (net (code "19") (name "AVCC") (class "Default")
      (node (ref "C8") (pin "1") (pinfunction "1_1") (pintype "passive"))
      (node (ref "C9") (pin "1") (pinfunction "1_1") (pintype "passive"))
      (node (ref "IC2") (pin "30") (pinfunction "AVDD_30") (pintype "bidirectional"))
      (node (ref "R3") (pin "2") (pinfunction "2_2") (pintype "passive"))
    )
    (net (code "20") (name "EMDC{slash}PMCS1") (class "Default")
      (node (ref "IC2") (pin "71") (pinfunction "EMDC/AEMDC/IC4/PMCS1/PMA14/RD11_71") (pintype "bidirectional"))
      (node (ref "J8") (pin "5") (pinfunction "5_5") (pintype "passive"))
    )
    (net (code "21") (name "EMDIO") (class "Default")
      (node (ref "IC2") (pin "68") (pinfunction "RTCC/EMDIO/AEMDIO/IC1/RD8_68") (pintype "bidirectional"))
      (node (ref "J8") (pin "6") (pinfunction "6_6") (pintype "passive"))
    )
    (net (code "22") (name "ERXD0") (class "Default")
      (node (ref "D5") (pin "1") (pinfunction "A1_1") (pintype "bidirectional"))
      (node (ref "IC2") (pin "41") (pinfunction "AN12/ERXD0/AECRS/PMA11/RB12_41") (pintype "bidirectional"))
      (node (ref "J8") (pin "12") (pinfunction "12_12") (pintype "passive"))
      (node (ref "R28") (pin "1") (pinfunction "1_1") (pintype "passive"))
    )
    (net (code "23") (name "ERXD1") (class "Default")
      (node (ref "D5") (pin "2") (pinfunction "A2_2") (pintype "bidirectional"))
      (node (ref "IC2") (pin "42") (pinfunction "AN13/ERXD1/AECOL/PMA10/RB13_42") (pintype "bidirectional"))
      (node (ref "J8") (pin "13") (pinfunction "13_13") (pintype "passive"))
      (node (ref "R29") (pin "1") (pinfunction "1_1") (pintype "passive"))
    )
    (net (code "24") (name "ERXERR") (class "Default")
      (node (ref "D4") (pin "5") (pinfunction "A2_5") (pintype "bidirectional"))
      (node (ref "IC2") (pin "35") (pinfunction "AN11/ERXERR/AETXERR/PMA12/RB11_35") (pintype "bidirectional"))
      (node (ref "J8") (pin "14") (pinfunction "14_14") (pintype "passive"))
      (node (ref "R27") (pin "1") (pinfunction "1_1") (pintype "passive"))
    )
    (net (code "25") (name "ETXD0") (class "Default")
      (node (ref "IC2") (pin "88") (pinfunction "C1TX/ETXD0/PMD10/RF1_88") (pintype "bidirectional"))
      (node (ref "J8") (pin "8") (pinfunction "8_8") (pintype "passive"))
    )
    (net (code "26") (name "ETXD1") (class "Default")
      (node (ref "IC2") (pin "87") (pinfunction "C1RX/ETXD1/PMD11/RF0_87") (pintype "bidirectional"))
      (node (ref "J8") (pin "9") (pinfunction "9_9") (pintype "passive"))
    )
    (net (code "27") (name "ETXEN{slash}RD6") (class "Default")
      (node (ref "IC2") (pin "83") (pinfunction "ETXEN/PMD14/CN15/RD6_83") (pintype "bidirectional"))
      (node (ref "J8") (pin "7") (pinfunction "7_7") (pintype "passive"))
    )
    (net (code "28") (name "GND") (class "Default")
      (node (ref "BTN1") (pin "1A") (pinfunction "1A_1A") (pintype "passive"))
      (node (ref "BTN1") (pin "2A") (pinfunction "2A_2A") (pintype "passive"))
      (node (ref "C1") (pin "2") (pinfunction "2_2") (pintype "passive"))
      (node (ref "C10") (pin "2") (pinfunction "2_2") (pintype "passive"))
      (node (ref "C11") (pin "2") (pinfunction "2_2") (pintype "passive"))
      (node (ref "C13") (pin "2") (pinfunction "2_2") (pintype "passive"))
      (node (ref "C14") (pin "2") (pinfunction "2_2") (pintype "passive"))
      (node (ref "C15") (pin "2") (pinfunction "2_2") (pintype "passive"))
      (node (ref "C16") (pin "2") (pinfunction "2_2") (pintype "passive"))
      (node (ref "C17") (pin "-") (pinfunction "-_-") (pintype "passive"))
      (node (ref "C18") (pin "2") (pinfunction "2_2") (pintype "passive"))
      (node (ref "C2") (pin "2") (pinfunction "2_2") (pintype "passive"))
      (node (ref "C20") (pin "2") (pinfunction "2_2") (pintype "passive"))
      (node (ref "C21") (pin "-") (pinfunction "-_-") (pintype "passive"))
      (node (ref "C22") (pin "2") (pinfunction "2_2") (pintype "passive"))
      (node (ref "C23") (pin "2") (pinfunction "2_2") (pintype "passive"))
      (node (ref "C24") (pin "2") (pinfunction "2_2") (pintype "passive"))
      (node (ref "C25") (pin "2") (pinfunction "2_2") (pintype "passive"))
      (node (ref "C26") (pin "-") (pinfunction "-_-") (pintype "passive"))
      (node (ref "C3") (pin "2") (pinfunction "2_2") (pintype "passive"))
      (node (ref "C4") (pin "2") (pinfunction "2_2") (pintype "passive"))
      (node (ref "C5") (pin "2") (pinfunction "2_2") (pintype "passive"))
      (node (ref "C6") (pin "2") (pinfunction "2_2") (pintype "passive"))
      (node (ref "C7") (pin "2") (pinfunction "2_2") (pintype "passive"))
      (node (ref "C8") (pin "2") (pinfunction "2_2") (pintype "passive"))
      (node (ref "C9") (pin "2") (pinfunction "2_2") (pintype "passive"))
      (node (ref "D1") (pin "1") (pinfunction "CAT_1") (pintype "bidirectional"))
      (node (ref "D8") (pin "2") (pinfunction "COM_2") (pintype "bidirectional"))
      (node (ref "D9") (pin "1") (pinfunction "CAT_1") (pintype "bidirectional"))
      (node (ref "IC1") (pin "17") (pinfunction "GND_17") (pintype "bidirectional"))
      (node (ref "IC1") (pin "20") (pinfunction "GND_20") (pintype "bidirectional"))
      (node (ref "IC1") (pin "24") (pinfunction "AGND_24") (pintype "bidirectional"))
      (node (ref "IC1") (pin "26") (pinfunction "TEST_26") (pintype "bidirectional"))
      (node (ref "IC1") (pin "4") (pinfunction "GND_4") (pintype "bidirectional"))
      (node (ref "IC2") (pin "15") (pinfunction "VSS_15") (pintype "bidirectional"))
      (node (ref "IC2") (pin "31") (pinfunction "AVSS_31") (pintype "bidirectional"))
      (node (ref "IC2") (pin "36") (pinfunction "VSS_36") (pintype "bidirectional"))
      (node (ref "IC2") (pin "45") (pinfunction "VSS_45") (pintype "bidirectional"))
      (node (ref "IC2") (pin "65") (pinfunction "VSS_65") (pintype "bidirectional"))
      (node (ref "IC2") (pin "75") (pinfunction "VSS_75") (pintype "bidirectional"))
      (node (ref "IC3") (pin "4") (pinfunction "GND_4") (pintype "bidirectional"))
      (node (ref "IC3") (pin "PAD") (pinfunction "PAD_PAD") (pintype "bidirectional"))
      (node (ref "IC5") (pin "2") (pinfunction "GND_2") (pintype "bidirectional"))
      (node (ref "J1") (pin "5") (pinfunction "G_5") (pintype "bidirectional"))
      (node (ref "J1") (pin "S1") (pinfunction "SH1_S1") (pintype "bidirectional"))
      (node (ref "J1") (pin "S2") (pinfunction "SH2_S2") (pintype "bidirectional"))
      (node (ref "J1") (pin "S3") (pinfunction "SH3_S3") (pintype "bidirectional"))
      (node (ref "J1") (pin "S4") (pinfunction "SH4_S4") (pintype "bidirectional"))
      (node (ref "J1") (pin "S5") (pinfunction "SH5_S5") (pintype "bidirectional"))
      (node (ref "J1") (pin "S6") (pinfunction "SH6_S6") (pintype "bidirectional"))
      (node (ref "J10") (pin "6") (pinfunction "6_6") (pintype "passive"))
      (node (ref "J10") (pin "7") (pinfunction "7_7") (pintype "passive"))
      (node (ref "J11") (pin "3") (pinfunction "3_3") (pintype "passive"))
      (node (ref "J13") (pin "6") (pinfunction "6_6") (pintype "passive"))
      (node (ref "J15") (pin "1") (pinfunction "1_1") (pintype "passive"))
      (node (ref "J15") (pin "2") (pinfunction "2_2") (pintype "passive"))
      (node (ref "J16") (pin "1") (pinfunction "1_1") (pintype "passive"))
      (node (ref "J17") (pin "1") (pinfunction "1_1") (pintype "passive"))
      (node (ref "J2") (pin "2") (pinfunction "2_2") (pintype "passive"))
      (node (ref "J2") (pin "3") (pinfunction "3_3") (pintype "passive"))
      (node (ref "J3") (pin "13") (pinfunction "13_13") (pintype "passive"))
      (node (ref "LD3") (pin "C") (pinfunction "C_C") (pintype "passive"))
      (node (ref "Q2") (pin "1") (pinfunction "E_1") (pintype "bidirectional"))
      (node (ref "Q2") (pin "4") (pinfunction "E_4") (pintype "bidirectional"))
      (node (ref "R14") (pin "1") (pinfunction "1_1") (pintype "passive"))
      (node (ref "R36") (pin "1") (pinfunction "1_1") (pintype "passive"))
      (node (ref "R9") (pin "1") (pinfunction "1_1") (pintype "passive"))
    )
    (net (code "29") (name "IC5") (class "Default")
      (node (ref "IC2") (pin "79") (pinfunction "ETXD2/IC5/PMD12/RD12_79") (pintype "bidirectional"))
      (node (ref "J3") (pin "1") (pinfunction "1_1") (pintype "passive"))
    )
    (net (code "30") (name "INT1{slash}RE8") (class "Default")
      (node (ref "IC2") (pin "18") (pinfunction "AERXD0/INT1/RE8_18") (pintype "bidirectional"))
      (node (ref "J14") (pin "5") (pinfunction "5_5") (pintype "passive"))
    )
    (net (code "31") (name "INT2{slash}RE9") (class "Default")
      (node (ref "IC2") (pin "19") (pinfunction "AERXD1/INT2/RE9_19") (pintype "bidirectional"))
      (node (ref "J14") (pin "15") (pinfunction "15_15") (pintype "passive"))
    )
    (net (code "32") (name "MISO") (class "Default")
      (node (ref "J13") (pin "1") (pinfunction "1_1") (pintype "passive"))
      (node (ref "J8") (pin "4") (pinfunction "4_4") (pintype "passive"))
      (node (ref "JP3") (pin "2") (pinfunction "2_2") (pintype "passive"))
    )
    (net (code "33") (name "MOSI") (class "Default")
      (node (ref "J13") (pin "4") (pinfunction "4_4") (pintype "passive"))
      (node (ref "J8") (pin "3") (pinfunction "3_3") (pintype "passive"))
      (node (ref "JP4") (pin "2") (pinfunction "2_2") (pintype "passive"))
    )
    (net (code "34") (name "Net-(BTN1-Pad1B)") (class "Default")
      (node (ref "BTN1") (pin "1B") (pinfunction "1B_1B") (pintype "passive"))
      (node (ref "BTN1") (pin "2B") (pinfunction "2B_2B") (pintype "passive"))
      (node (ref "R8") (pin "1") (pinfunction "1_1") (pintype "passive"))
    )
    (net (code "35") (name "Net-(C16-Pad1)") (class "Default")
      (node (ref "C16") (pin "1") (pinfunction "1_1") (pintype "passive"))
      (node (ref "R44") (pin "1") (pinfunction "1_1") (pintype "passive"))
    )
    (net (code "36") (name "Net-(C22-Pad1)") (class "Default")
      (node (ref "C22") (pin "1") (pinfunction "1_1") (pintype "passive"))
      (node (ref "R32") (pin "1") (pinfunction "1_1") (pintype "passive"))
      (node (ref "X1") (pin "1") (pinfunction "1_1") (pintype "passive"))
    )
    (net (code "37") (name "Net-(D1-COM)") (class "Default")
      (node (ref "D1") (pin "3") (pinfunction "COM_3") (pintype "bidirectional"))
      (node (ref "IC2") (pin "13") (pinfunction "MCLR_13") (pintype "bidirectional"))
      (node (ref "R39") (pin "1") (pinfunction "1_1") (pintype "passive"))
    )
    (net (code "38") (name "Net-(D2-PadA)") (class "Default")
      (node (ref "D2") (pin "A") (pinfunction "A_A") (pintype "bidirectional"))
      (node (ref "JP1") (pin "3") (pinfunction "3_3") (pintype "passive"))
    )
    (net (code "39") (name "Net-(D3A-A1)") (class "Default")
      (node (ref "D3") (pin "1") (pinfunction "A1_1") (pintype "bidirectional"))
      (node (ref "IC2") (pin "25") (pinfunction "PGED1/AN0/CN2/RB0_25") (pintype "bidirectional"))
      (node (ref "R16") (pin "1") (pinfunction "1_1") (pintype "passive"))
    )
    (net (code "40") (name "Net-(D3A-A2)") (class "Default")
      (node (ref "D3") (pin "2") (pinfunction "A2_2") (pintype "bidirectional"))
      (node (ref "IC2") (pin "24") (pinfunction "PGEC1/AN1/CN3/RB1_24") (pintype "bidirectional"))
      (node (ref "R17") (pin "1") (pinfunction "1_1") (pintype "passive"))
    )
    (net (code "41") (name "Net-(D3B-A1)") (class "Default")
      (node (ref "D3") (pin "4") (pinfunction "A1_4") (pintype "bidirectional"))
      (node (ref "IC2") (pin "23") (pinfunction "AN2/C2IN-/CN4/RB2_23") (pintype "bidirectional"))
      (node (ref "R18") (pin "1") (pinfunction "1_1") (pintype "passive"))
    )
    (net (code "42") (name "Net-(D3B-A2)") (class "Default")
      (node (ref "D3") (pin "5") (pinfunction "A2_5") (pintype "bidirectional"))
      (node (ref "IC2") (pin "22") (pinfunction "AN3/C2IN+/CN5/RB3_22") (pintype "bidirectional"))
      (node (ref "R19") (pin "1") (pinfunction "1_1") (pintype "passive"))
    )
    (net (code "43") (name "Net-(D4A-A1)") (class "Default")
      (node (ref "D4") (pin "1") (pinfunction "A1_1") (pintype "bidirectional"))
      (node (ref "IC2") (pin "32") (pinfunction "AN8/C1OUT/RB8_32") (pintype "bidirectional"))
      (node (ref "R24") (pin "1") (pinfunction "1_1") (pintype "passive"))
    )
    (net (code "44") (name "Net-(D4A-A2)") (class "Default")
      (node (ref "D4") (pin "2") (pinfunction "A2_2") (pintype "bidirectional"))
      (node (ref "IC2") (pin "33") (pinfunction "AN9/C2OUT/RB9_33") (pintype "bidirectional"))
      (node (ref "R25") (pin "1") (pinfunction "1_1") (pintype "passive"))
    )
    (net (code "45") (name "Net-(D4B-A1)") (class "Default")
      (node (ref "D4") (pin "4") (pinfunction "A1_4") (pintype "bidirectional"))
      (node (ref "IC2") (pin "34") (pinfunction "AN10/CVREFOUT/PMA13/RB10_34") (pintype "bidirectional"))
      (node (ref "R26") (pin "1") (pinfunction "1_1") (pintype "passive"))
    )
    (net (code "46") (name "Net-(D5B-A1)") (class "Default")
      (node (ref "D5") (pin "4") (pinfunction "A1_4") (pintype "bidirectional"))
      (node (ref "IC2") (pin "43") (pinfunction "AN14/ERXD2/AETXD3/PMALH/PMA1/RB14_43") (pintype "bidirectional"))
      (node (ref "R30") (pin "1") (pinfunction "1_1") (pintype "passive"))
    )
    (net (code "47") (name "Net-(D5B-A2)") (class "Default")
      (node (ref "D5") (pin "5") (pinfunction "A2_5") (pintype "bidirectional"))
      (node (ref "IC2") (pin "44") (pinfunction "OCFB/PMALL/PMA0/CN12/RB15_44") (pintype "bidirectional"))
      (node (ref "R31") (pin "1") (pinfunction "1_1") (pintype "passive"))
    )
    (net (code "48") (name "Net-(D6A-A1)") (class "Default")
      (node (ref "D6") (pin "1") (pinfunction "A1_1") (pintype "bidirectional"))
      (node (ref "IC2") (pin "21") (pinfunction "AN4/C1IN-/CN6/RB4_21") (pintype "bidirectional"))
      (node (ref "R20") (pin "1") (pinfunction "1_1") (pintype "passive"))
    )
    (net (code "49") (name "Net-(D6A-A2)") (class "Default")
      (node (ref "D6") (pin "2") (pinfunction "A2_2") (pintype "bidirectional"))
      (node (ref "IC2") (pin "20") (pinfunction "AN5/C1IN+/VBUSON/CN7/RB5_20") (pintype "bidirectional"))
      (node (ref "R21") (pin "1") (pinfunction "1_1") (pintype "passive"))
    )
    (net (code "50") (name "Net-(D7A-A1)") (class "Default")
      (node (ref "D7") (pin "1") (pinfunction "A1_1") (pintype "bidirectional"))
      (node (ref "IC2") (pin "28") (pinfunction "VREF-/CVREF-/AERXD2/PMA7/RA9_28") (pintype "bidirectional"))
      (node (ref "R33") (pin "1") (pinfunction "1_1") (pintype "passive"))
    )
    (net (code "51") (name "Net-(D7A-A2)") (class "Default")
      (node (ref "D7") (pin "2") (pinfunction "A2_2") (pintype "bidirectional"))
      (node (ref "IC2") (pin "29") (pinfunction "VREF+/CVREF+/AERXD3/PMA6/RA10_29") (pintype "bidirectional"))
      (node (ref "R15") (pin "1") (pinfunction "1_1") (pintype "passive"))
    )
    (net (code "52") (name "Net-(D7B-A1)") (class "Default")
      (node (ref "D7") (pin "4") (pinfunction "A1_4") (pintype "bidirectional"))
      (node (ref "IC2") (pin "74") (pinfunction "SOSCO/T1CK/CN0/RC14_74") (pintype "bidirectional"))
      (node (ref "R6") (pin "1") (pinfunction "1_1") (pintype "passive"))
    )
    (net (code "53") (name "Net-(D7B-A2)") (class "Default")
      (node (ref "D7") (pin "5") (pinfunction "A2_5") (pintype "bidirectional"))
      (node (ref "IC2") (pin "73") (pinfunction "SOSCI/CN1/RC13_73") (pintype "bidirectional"))
      (node (ref "R5") (pin "1") (pinfunction "1_1") (pintype "passive"))
    )
    (net (code "54") (name "Net-(D8-D3)") (class "Default")
      (node (ref "D8") (pin "4") (pinfunction "D3_4") (pintype "bidirectional"))
      (node (ref "J11") (pin "4") (pinfunction "4_4") (pintype "passive"))
      (node (ref "R40") (pin "2") (pinfunction "2_2") (pintype "passive"))
    )
    (net (code "55") (name "Net-(D8-D4)") (class "Default")
      (node (ref "D8") (pin "5") (pinfunction "D4_5") (pintype "bidirectional"))
      (node (ref "J11") (pin "5") (pinfunction "5_5") (pintype "passive"))
      (node (ref "R41") (pin "2") (pinfunction "2_2") (pintype "passive"))
    )
    (net (code "56") (name "Net-(IC1-CBUS0)") (class "Default")
      (node (ref "IC1") (pin "22") (pinfunction "CBUS0_22") (pintype "bidirectional"))
      (node (ref "LD1") (pin "C") (pinfunction "C_C") (pintype "passive"))
    )
    (net (code "57") (name "Net-(IC1-CBUS1)") (class "Default")
      (node (ref "IC1") (pin "21") (pinfunction "CBUS1_21") (pintype "bidirectional"))
      (node (ref "LD2") (pin "C") (pinfunction "C_C") (pintype "passive"))
    )
    (net (code "58") (name "Net-(IC1-CTS#)") (class "Default")
      (node (ref "IC1") (pin "8") (pinfunction "CTS#_8") (pintype "bidirectional"))
      (node (ref "J12") (pin "1") (pinfunction "1_1") (pintype "passive"))
    )
    (net (code "59") (name "Net-(IC1-DCD#)") (class "Default")
      (node (ref "IC1") (pin "7") (pinfunction "DCD#_7") (pintype "bidirectional"))
      (node (ref "J12") (pin "3") (pinfunction "3_3") (pintype "passive"))
    )
    (net (code "60") (name "Net-(IC1-DSR#)") (class "Default")
      (node (ref "IC1") (pin "6") (pinfunction "DSR#_6") (pintype "bidirectional"))
      (node (ref "J12") (pin "2") (pinfunction "2_2") (pintype "passive"))
    )
    (net (code "61") (name "Net-(IC1-DTR#)") (class "Default")
      (node (ref "C12") (pin "1") (pinfunction "1_1") (pintype "passive"))
      (node (ref "IC1") (pin "31") (pinfunction "DTR#_31") (pintype "bidirectional"))
    )
    (net (code "62") (name "Net-(IC1-RESET#)") (class "Default")
      (node (ref "C1") (pin "1") (pinfunction "1_1") (pintype "passive"))
      (node (ref "IC1") (pin "18") (pinfunction "RESET#_18") (pintype "bidirectional"))
      (node (ref "R7") (pin "1") (pinfunction "1_1") (pintype "passive"))
      (node (ref "R9") (pin "2") (pinfunction "2_2") (pintype "passive"))
    )
    (net (code "63") (name "Net-(IC1-RI#)") (class "Default")
      (node (ref "IC1") (pin "3") (pinfunction "RI#_3") (pintype "bidirectional"))
      (node (ref "J12") (pin "4") (pinfunction "4_4") (pintype "passive"))
    )
    (net (code "64") (name "Net-(IC1-RTS#)") (class "Default")
      (node (ref "IC1") (pin "32") (pinfunction "RTS#_32") (pintype "bidirectional"))
      (node (ref "R38") (pin "1") (pinfunction "1_1") (pintype "passive"))
    )
    (net (code "65") (name "Net-(IC1-RXD)") (class "Default")
      (node (ref "IC1") (pin "2") (pinfunction "RXD_2") (pintype "bidirectional"))
      (node (ref "R2") (pin "1") (pinfunction "1_1") (pintype "passive"))
    )
    (net (code "66") (name "Net-(IC1-TXD)") (class "Default")
      (node (ref "IC1") (pin "30") (pinfunction "TXD_30") (pintype "bidirectional"))
      (node (ref "R1") (pin "1") (pinfunction "1_1") (pintype "passive"))
    )
    (net (code "67") (name "Net-(IC1-USBDM)") (class "Default")
      (node (ref "IC1") (pin "15") (pinfunction "USBDM_15") (pintype "bidirectional"))
      (node (ref "J1") (pin "2") (pinfunction "D-_2") (pintype "bidirectional"))
    )
    (net (code "68") (name "Net-(IC1-USBDP)") (class "Default")
      (node (ref "IC1") (pin "14") (pinfunction "USBDP_14") (pintype "bidirectional"))
      (node (ref "J1") (pin "3") (pinfunction "D+_3") (pintype "bidirectional"))
    )
    (net (code "69") (name "Net-(IC2A-VCAP{slash}VDDCORE)") (class "Default")
      (node (ref "C10") (pin "1") (pinfunction "1_1") (pintype "passive"))
      (node (ref "IC2") (pin "85") (pinfunction "VCAP/VDDCORE_85") (pintype "bidirectional"))
    )
    (net (code "70") (name "Net-(IC2D-OSC1{slash}CLKI{slash}RC12)") (class "Default")
      (node (ref "C23") (pin "1") (pinfunction "1_1") (pintype "passive"))
      (node (ref "IC2") (pin "63") (pinfunction "OSC1/CLKI/RC12_63") (pintype "bidirectional"))
      (node (ref "X1") (pin "3") (pinfunction "2_3") (pintype "passive"))
    )
    (net (code "71") (name "Net-(IC2D-OSC2{slash}CLKO{slash}RC15)") (class "Default")
      (node (ref "IC2") (pin "64") (pinfunction "OSC2/CLKO/RC15_64") (pintype "bidirectional"))
      (node (ref "R32") (pin "2") (pinfunction "2_2") (pintype "passive"))
    )
    (net (code "72") (name "Net-(IC3-CDELAY)") (class "Default")
      (node (ref "C14") (pin "1") (pinfunction "1_1") (pintype "passive"))
      (node (ref "IC3") (pin "6") (pinfunction "CDELAY_6") (pintype "bidirectional"))
    )
    (net (code "73") (name "Net-(IC4-ADJ)") (class "Default")
      (node (ref "IC4") (pin "1") (pinfunction "ADJ_1") (pintype "power_in"))
      (node (ref "R36") (pin "2") (pinfunction "2_2") (pintype "passive"))
      (node (ref "R37") (pin "1") (pinfunction "1_1") (pintype "passive"))
    )
    (net (code "74") (name "Net-(IC4-IN)") (class "Default")
      (node (ref "C15") (pin "1") (pinfunction "1_1") (pintype "passive"))
      (node (ref "C26") (pin "+") (pinfunction "+_+") (pintype "passive"))
      (node (ref "D2") (pin "C") (pinfunction "C_C") (pintype "bidirectional"))
      (node (ref "IC4") (pin "3") (pinfunction "IN_3") (pintype "power_in"))
    )
    (net (code "75") (name "Net-(IC5A-OUT)") (class "Default")
      (node (ref "IC5") (pin "1") (pinfunction "OUT_1") (pintype "output"))
      (node (ref "Q1") (pin "1") (pinfunction "G_1") (pintype "bidirectional"))
    )
    (net (code "76") (name "Net-(LD1-PadA)") (class "Default")
      (node (ref "LD1") (pin "A") (pinfunction "A_A") (pintype "passive"))
      (node (ref "R10") (pin "1") (pinfunction "1_1") (pintype "passive"))
    )
    (net (code "77") (name "Net-(LD2-PadA)") (class "Default")
      (node (ref "LD2") (pin "A") (pinfunction "A_A") (pintype "passive"))
      (node (ref "R11") (pin "1") (pinfunction "1_1") (pintype "passive"))
    )
    (net (code "78") (name "Net-(LD3-PadA)") (class "Default")
      (node (ref "LD3") (pin "A") (pinfunction "A_A") (pintype "passive"))
      (node (ref "R12") (pin "1") (pinfunction "1_1") (pintype "passive"))
    )
    (net (code "79") (name "Net-(LD4-PadC)") (class "Default")
      (node (ref "LD4") (pin "C") (pinfunction "C_C") (pintype "passive"))
      (node (ref "R34") (pin "2") (pinfunction "2_2") (pintype "passive"))
    )
    (net (code "80") (name "Net-(LD5-PadC)") (class "Default")
      (node (ref "LD5") (pin "C") (pinfunction "C_C") (pintype "passive"))
      (node (ref "R42") (pin "2") (pinfunction "2_2") (pintype "passive"))
    )
    (net (code "81") (name "Net-(Q2A-B)") (class "Default")
      (node (ref "Q2") (pin "5") (pinfunction "B_5") (pintype "bidirectional"))
      (node (ref "R35") (pin "2") (pinfunction "2_2") (pintype "passive"))
    )
    (net (code "82") (name "Net-(Q2A-C)") (class "Default")
      (node (ref "Q2") (pin "3") (pinfunction "C_3") (pintype "bidirectional"))
      (node (ref "R34") (pin "1") (pinfunction "1_1") (pintype "passive"))
    )
    (net (code "83") (name "Net-(Q2B-B)") (class "Default")
      (node (ref "Q2") (pin "2") (pinfunction "B_2") (pintype "bidirectional"))
      (node (ref "R43") (pin "2") (pinfunction "2_2") (pintype "passive"))
    )
    (net (code "84") (name "Net-(Q2B-C)") (class "Default")
      (node (ref "Q2") (pin "6") (pinfunction "C_6") (pintype "bidirectional"))
      (node (ref "R42") (pin "1") (pinfunction "1_1") (pintype "passive"))
    )
    (net (code "85") (name "OC1{slash}RD0") (class "Default")
      (node (ref "IC2") (pin "72") (pinfunction "SDO1/OC1/INT0/RD0_72") (pintype "bidirectional"))
      (node (ref "J14") (pin "7") (pinfunction "7_7") (pintype "passive"))
    )
    (net (code "86") (name "OC2{slash}RD1") (class "Default")
      (node (ref "IC2") (pin "76") (pinfunction "OC2/RD1_76") (pintype "bidirectional"))
      (node (ref "J14") (pin "11") (pinfunction "11_11") (pintype "passive"))
    )
    (net (code "87") (name "OC3{slash}RD2") (class "Default")
      (node (ref "IC2") (pin "77") (pinfunction "OC3/RD2_77") (pintype "bidirectional"))
      (node (ref "J14") (pin "13") (pinfunction "13_13") (pintype "passive"))
    )
    (net (code "88") (name "OC4{slash}RD3") (class "Default")
      (node (ref "IC2") (pin "78") (pinfunction "OC4/RD3_78") (pintype "bidirectional"))
      (node (ref "J3") (pin "3") (pinfunction "3_3") (pintype "passive"))
    )
    (net (code "89") (name "OC5{slash}PMWR{slash}RD4") (class "Default")
      (node (ref "IC2") (pin "81") (pinfunction "OC5/PMWR/CN13/RD4_81") (pintype "bidirectional"))
      (node (ref "J3") (pin "5") (pinfunction "5_5") (pintype "passive"))
    )
    (net (code "90") (name "P32_MCLR") (class "Default")
      (node (ref "C12") (pin "2") (pinfunction "2_2") (pintype "passive"))
      (node (ref "D8") (pin "3") (pinfunction "D2_3") (pintype "bidirectional"))
      (node (ref "J10") (pin "3") (pinfunction "3_3") (pintype "passive"))
      (node (ref "J11") (pin "1") (pinfunction "1_1") (pintype "passive"))
      (node (ref "JP5") (pin "1") (pinfunction "1_1") (pintype "passive"))
      (node (ref "JP5") (pin "2") (pinfunction "2_2") (pintype "passive"))
      (node (ref "R38") (pin "2") (pinfunction "2_2") (pintype "passive"))
      (node (ref "R39") (pin "2") (pinfunction "2_2") (pintype "passive"))
      (node (ref "R4") (pin "1") (pinfunction "1_1") (pintype "passive"))
      (node (ref "R8") (pin "2") (pinfunction "2_2") (pintype "passive"))
    )
    (net (code "91") (name "P32_PGC") (class "Default")
      (node (ref "D6") (pin "4") (pinfunction "A1_4") (pintype "bidirectional"))
      (node (ref "IC2") (pin "26") (pinfunction "PGEC2/AN6/OCFA/RB6_26") (pintype "bidirectional"))
      (node (ref "R22") (pin "1") (pinfunction "1_1") (pintype "passive"))
      (node (ref "R41") (pin "1") (pinfunction "1_1") (pintype "passive"))
    )
    (net (code "92") (name "P32_PGD") (class "Default")
      (node (ref "D6") (pin "5") (pinfunction "A2_5") (pintype "bidirectional"))
      (node (ref "IC2") (pin "27") (pinfunction "PGED2/AN7/RB7_27") (pintype "bidirectional"))
      (node (ref "R23") (pin "1") (pinfunction "1_1") (pintype "passive"))
      (node (ref "R40") (pin "1") (pinfunction "1_1") (pintype "passive"))
    )
    (net (code "93") (name "PMA2{slash}EREFCLK{slash}SS2A{slash}RG9") (class "Default")
      (node (ref "IC2") (pin "14") (pinfunction "SS2/U6RX/U3CTS/PMA2/CN11/RG9_14") (pintype "bidirectional"))
      (node (ref "J13") (pin "5") (pinfunction "5_5") (pintype "passive"))
      (node (ref "J8") (pin "1") (pinfunction "1_1") (pintype "passive"))
      (node (ref "JP2") (pin "1") (pinfunction "1_1") (pintype "passive"))
      (node (ref "JP2") (pin "2") (pinfunction "2_2") (pintype "passive"))
    )
    (net (code "94") (name "PMA3{slash}ECRSDV{slash}SDO2A{slash}RG8") (class "Default")
      (node (ref "IC2") (pin "12") (pinfunction "SCL4/SDO2/U3TX/PMA3/CN10/RG8_12") (pintype "bidirectional"))
      (node (ref "J8") (pin "11") (pinfunction "11_11") (pintype "passive"))
      (node (ref "JP3") (pin "3") (pinfunction "3_3") (pintype "passive"))
      (node (ref "JP4") (pin "1") (pinfunction "1_1") (pintype "passive"))
    )
    (net (code "95") (name "PMA4{slash}SDI2A{slash}RG7") (class "Default")
      (node (ref "IC2") (pin "11") (pinfunction "ECRS/SDA4/SDI2/U3RX/PMA4/CN9/RG7_11") (pintype "bidirectional"))
      (node (ref "J9") (pin "9") (pinfunction "9_9") (pintype "passive"))
      (node (ref "JP3") (pin "1") (pinfunction "1_1") (pintype "passive"))
      (node (ref "JP4") (pin "3") (pinfunction "3_3") (pintype "passive"))
    )
    (net (code "96") (name "PMA5{slash}SCK2A{slash}RG6") (class "Default")
      (node (ref "IC2") (pin "10") (pinfunction "ECOL/SCK2/U6TX/U3RTS/PMA5/CN8/RG6_10") (pintype "bidirectional"))
      (node (ref "J13") (pin "3") (pinfunction "3_3") (pintype "passive"))
      (node (ref "J8") (pin "2") (pinfunction "2_2") (pintype "passive"))
    )
    (net (code "97") (name "PMCS2") (class "Default")
      (node (ref "IC2") (pin "70") (pinfunction "SCK1/IC3/PMCS2/PMA15/RD10_70") (pintype "bidirectional"))
      (node (ref "J8") (pin "16") (pinfunction "16_16") (pintype "passive"))
    )
    (net (code "98") (name "PMD0") (class "Default")
      (node (ref "IC2") (pin "93") (pinfunction "PMD0/RE0_93") (pintype "bidirectional"))
      (node (ref "J9") (pin "1") (pinfunction "1_1") (pintype "passive"))
    )
    (net (code "99") (name "PMD1") (class "Default")
      (node (ref "IC2") (pin "94") (pinfunction "PMD1/RE1_94") (pintype "bidirectional"))
      (node (ref "J9") (pin "2") (pinfunction "2_2") (pintype "passive"))
    )
    (net (code "100") (name "PMD2") (class "Default")
      (node (ref "IC2") (pin "98") (pinfunction "PMD2/RE2_98") (pintype "bidirectional"))
      (node (ref "J9") (pin "3") (pinfunction "3_3") (pintype "passive"))
    )
    (net (code "101") (name "PMD3") (class "Default")
      (node (ref "IC2") (pin "99") (pinfunction "PMD3/RE3_99") (pintype "bidirectional"))
      (node (ref "J9") (pin "4") (pinfunction "4_4") (pintype "passive"))
    )
    (net (code "102") (name "PMD4") (class "Default")
      (node (ref "IC2") (pin "100") (pinfunction "PMD4/RE4_100") (pintype "bidirectional"))
      (node (ref "J9") (pin "5") (pinfunction "5_5") (pintype "passive"))
    )
    (net (code "103") (name "PMD5") (class "Default")
      (node (ref "IC2") (pin "3") (pinfunction "PMD5/RE5_3") (pintype "bidirectional"))
      (node (ref "J9") (pin "6") (pinfunction "6_6") (pintype "passive"))
    )
    (net (code "104") (name "PMD6") (class "Default")
      (node (ref "IC2") (pin "4") (pinfunction "PMD6/RE6_4") (pintype "bidirectional"))
      (node (ref "J9") (pin "7") (pinfunction "7_7") (pintype "passive"))
    )
    (net (code "105") (name "PMD7") (class "Default")
      (node (ref "IC2") (pin "5") (pinfunction "PMD7/RE7_5") (pintype "bidirectional"))
      (node (ref "J9") (pin "8") (pinfunction "8_8") (pintype "passive"))
    )
    (net (code "106") (name "PMRD{slash}RD5") (class "Default")
      (node (ref "IC2") (pin "82") (pinfunction "PMRD/CN14/RD5_82") (pintype "bidirectional"))
      (node (ref "J8") (pin "15") (pinfunction "15_15") (pintype "passive"))
    )
    (net (code "107") (name "RA0") (class "Default")
      (node (ref "IC2") (pin "17") (pinfunction "TMS/RA0_17") (pintype "bidirectional"))
      (node (ref "J14") (pin "2") (pinfunction "2_2") (pintype "passive"))
    )
    (net (code "108") (name "RA1") (class "Default")
      (node (ref "IC2") (pin "38") (pinfunction "TCK/RA1_38") (pintype "bidirectional"))
      (node (ref "J14") (pin "4") (pinfunction "4_4") (pintype "passive"))
    )
    (net (code "109") (name "RA4") (class "Default")
      (node (ref "IC2") (pin "60") (pinfunction "TDI/RA4_60") (pintype "bidirectional"))
      (node (ref "J14") (pin "6") (pinfunction "6_6") (pintype "passive"))
    )
    (net (code "110") (name "RA5") (class "Default")
      (node (ref "IC2") (pin "61") (pinfunction "TDO/RA5_61") (pintype "bidirectional"))
      (node (ref "J14") (pin "8") (pinfunction "8_8") (pintype "passive"))
    )
    (net (code "111") (name "RA6") (class "Default")
      (node (ref "IC2") (pin "91") (pinfunction "TRCLK/RA6_91") (pintype "bidirectional"))
      (node (ref "J3") (pin "6") (pinfunction "6_6") (pintype "passive"))
    )
    (net (code "112") (name "RA7") (class "Default")
      (node (ref "IC2") (pin "92") (pinfunction "TRD3/RA7_92") (pintype "bidirectional"))
      (node (ref "J3") (pin "8") (pinfunction "8_8") (pintype "passive"))
    )
    (net (code "113") (name "RC13") (class "Default")
      (node (ref "J14") (pin "12") (pinfunction "12_12") (pintype "passive"))
      (node (ref "R5") (pin "2") (pinfunction "2_2") (pintype "passive"))
    )
    (net (code "114") (name "RD7") (class "Default")
      (node (ref "IC2") (pin "84") (pinfunction "ETXCLK/PMD15/CN16/RD7_84") (pintype "bidirectional"))
      (node (ref "J14") (pin "16") (pinfunction "16_16") (pintype "passive"))
    )
    (net (code "115") (name "RD9") (class "Default")
      (node (ref "IC2") (pin "69") (pinfunction "SS1/IC2/RD9_69") (pintype "bidirectional"))
      (node (ref "J14") (pin "10") (pinfunction "10_10") (pintype "passive"))
    )
    (net (code "116") (name "RD13") (class "Default")
      (node (ref "IC2") (pin "80") (pinfunction "ETXD3/PMD13/CN19/RD13_80") (pintype "bidirectional"))
      (node (ref "J14") (pin "14") (pinfunction "14_14") (pintype "passive"))
    )
    (net (code "117") (name "RG0") (class "Default")
      (node (ref "IC2") (pin "90") (pinfunction "C2RX/PMD8/RG0_90") (pintype "bidirectional"))
      (node (ref "J3") (pin "4") (pinfunction "4_4") (pintype "passive"))
    )
    (net (code "118") (name "RG1") (class "Default")
      (node (ref "IC2") (pin "89") (pinfunction "C2TX/ETXERR/PMD9/RG1_89") (pintype "bidirectional"))
      (node (ref "J3") (pin "2") (pinfunction "2_2") (pintype "passive"))
    )
    (net (code "119") (name "RG12") (class "Default")
      (node (ref "IC2") (pin "96") (pinfunction "TRD1/RG12_96") (pintype "bidirectional"))
      (node (ref "J3") (pin "12") (pinfunction "12_12") (pintype "passive"))
    )
    (net (code "120") (name "RG13") (class "Default")
      (node (ref "IC2") (pin "97") (pinfunction "TRD0/RG13_97") (pintype "bidirectional"))
      (node (ref "J3") (pin "14") (pinfunction "14_14") (pintype "passive"))
    )
    (net (code "121") (name "RG14") (class "Default")
      (node (ref "IC2") (pin "95") (pinfunction "TRD2/RG14_95") (pintype "bidirectional"))
      (node (ref "J3") (pin "10") (pinfunction "10_10") (pintype "passive"))
    )
    (net (code "122") (name "RG15") (class "Default")
      (node (ref "IC2") (pin "1") (pinfunction "AERXERR/RG15_1") (pintype "bidirectional"))
      (node (ref "J9") (pin "10") (pinfunction "10_10") (pintype "passive"))
    )
    (net (code "123") (name "SCL1") (class "Default")
      (node (ref "IC2") (pin "66") (pinfunction "AETXCLK/SCL1/INT3/RA14_66") (pintype "bidirectional"))
      (node (ref "J18") (pin "1") (pinfunction "1_1") (pintype "passive"))
      (node (ref "J4") (pin "1") (pinfunction "1_1") (pintype "passive"))
    )
    (net (code "124") (name "SCL2{slash}RA2") (class "Default")
      (node (ref "IC2") (pin "58") (pinfunction "SCL2/RA2_58") (pintype "bidirectional"))
      (node (ref "J3") (pin "9") (pinfunction "9_9") (pintype "passive"))
    )
    (net (code "125") (name "SDA1") (class "Default")
      (node (ref "IC2") (pin "67") (pinfunction "AETXEN/SDA1/INT4/RA15_67") (pintype "bidirectional"))
      (node (ref "J18") (pin "2") (pinfunction "2_2") (pintype "passive"))
      (node (ref "J4") (pin "2") (pinfunction "2_2") (pintype "passive"))
    )
    (net (code "126") (name "SDA2{slash}RA3") (class "Default")
      (node (ref "IC2") (pin "59") (pinfunction "SDA2/RA3_59") (pintype "bidirectional"))
      (node (ref "J3") (pin "11") (pinfunction "11_11") (pintype "passive"))
      (node (ref "R35") (pin "1") (pinfunction "1_1") (pintype "passive"))
    )
    (net (code "127") (name "T1CK{slash}RC14") (class "Default")
      (node (ref "J14") (pin "9") (pinfunction "9_9") (pintype "passive"))
      (node (ref "R6") (pin "2") (pinfunction "2_2") (pintype "passive"))
    )
    (net (code "128") (name "T2CK{slash}RC1") (class "Default")
      (node (ref "IC2") (pin "6") (pinfunction "T2CK/RC1_6") (pintype "bidirectional"))
      (node (ref "R43") (pin "1") (pinfunction "1_1") (pintype "passive"))
    )
    (net (code "129") (name "T5CK{slash}RC4") (class "Default")
      (node (ref "IC2") (pin "9") (pinfunction "T5CK/SDI1/RC4_9") (pintype "bidirectional"))
      (node (ref "J3") (pin "7") (pinfunction "7_7") (pintype "passive"))
    )
    (net (code "130") (name "U1ARX") (class "Default")
      (node (ref "IC2") (pin "52") (pinfunction "SDA3/SDI3/U1RX/RF2_52") (pintype "bidirectional"))
      (node (ref "J14") (pin "1") (pinfunction "1_1") (pintype "passive"))
      (node (ref "R1") (pin "2") (pinfunction "2_2") (pintype "passive"))
    )
    (net (code "131") (name "U1ATX") (class "Default")
      (node (ref "IC2") (pin "53") (pinfunction "SCL3/SDO3/U1TX/RF8_53") (pintype "bidirectional"))
      (node (ref "J14") (pin "3") (pinfunction "3_3") (pintype "passive"))
      (node (ref "R2") (pin "2") (pinfunction "2_2") (pintype "passive"))
    )
    (net (code "132") (name "U1BRX") (class "Default")
      (node (ref "IC2") (pin "47") (pinfunction "AETXD0/SS3/U4RX/U1CTS/CN20/RD14_47") (pintype "bidirectional"))
      (node (ref "J4") (pin "3") (pinfunction "3_3") (pintype "passive"))
    )
    (net (code "133") (name "U1BTX") (class "Default")
      (node (ref "IC2") (pin "48") (pinfunction "AETXD1/SCK3/U4TX/U1RTS/CN21/RD15_48") (pintype "bidirectional"))
      (node (ref "J4") (pin "4") (pinfunction "4_4") (pintype "passive"))
    )
    (net (code "134") (name "U3ARX") (class "Default")
      (node (ref "IC2") (pin "49") (pinfunction "SDA5/SDI4/U2RX/PMA9/CN17/RF4_49") (pintype "bidirectional"))
      (node (ref "J4") (pin "5") (pinfunction "5_5") (pintype "passive"))
    )
    (net (code "135") (name "U3ATX") (class "Default")
      (node (ref "IC2") (pin "50") (pinfunction "SCL5/SDO4/U2TX/PMA8/CN18/RF5_50") (pintype "bidirectional"))
      (node (ref "J4") (pin "6") (pinfunction "6_6") (pintype "passive"))
    )
    (net (code "136") (name "U3BRX{slash}AC1RX{slash}RF12") (class "Default")
      (node (ref "IC2") (pin "40") (pinfunction "AC1RX/SS4/U5RX/U2CTS/RF12_40") (pintype "bidirectional"))
      (node (ref "J4") (pin "7") (pinfunction "7_7") (pintype "passive"))
    )
    (net (code "137") (name "U3BTX{slash}AC1TX{slash}RF13") (class "Default")
      (node (ref "IC2") (pin "39") (pinfunction "AC1TX/SCK4/U5TX/U2RTS/RF13_39") (pintype "bidirectional"))
      (node (ref "J4") (pin "8") (pinfunction "8_8") (pintype "passive"))
    )
    (net (code "138") (name "USB5V0") (class "Default")
      (node (ref "J1") (pin "1") (pinfunction "V_1") (pintype "bidirectional"))
      (node (ref "Q1") (pin "3") (pinfunction "D_3") (pintype "bidirectional"))
      (node (ref "R7") (pin "2") (pinfunction "2_2") (pintype "passive"))
    )
    (net (code "139") (name "USBD+") (class "Default")
      (node (ref "IC2") (pin "57") (pinfunction "D+/RG2_57") (pintype "bidirectional"))
      (node (ref "J9") (pin "11") (pinfunction "11_11") (pintype "passive"))
    )
    (net (code "140") (name "USBD-") (class "Default")
      (node (ref "IC2") (pin "56") (pinfunction "D-/RG3_56") (pintype "bidirectional"))
      (node (ref "J9") (pin "12") (pinfunction "12_12") (pintype "passive"))
    )
    (net (code "141") (name "USBID") (class "Default")
      (node (ref "IC2") (pin "51") (pinfunction "USBID/RF3_51") (pintype "bidirectional"))
      (node (ref "J9") (pin "13") (pinfunction "13_13") (pintype "passive"))
    )
    (net (code "142") (name "VBUS") (class "Default")
      (node (ref "IC2") (pin "54") (pinfunction "VBUS_54") (pintype "bidirectional"))
      (node (ref "J9") (pin "14") (pinfunction "14_14") (pintype "passive"))
    )
    (net (code "143") (name "VCC3V3") (class "Default")
      (node (ref "C11") (pin "1") (pinfunction "1_1") (pintype "passive"))
      (node (ref "C13") (pin "1") (pinfunction "1_1") (pintype "passive"))
      (node (ref "C18") (pin "1") (pinfunction "1_1") (pintype "passive"))
      (node (ref "C2") (pin "1") (pinfunction "1_1") (pintype "passive"))
      (node (ref "C21") (pin "+") (pinfunction "+_+") (pintype "passive"))
      (node (ref "C3") (pin "1") (pinfunction "1_1") (pintype "passive"))
      (node (ref "C4") (pin "1") (pinfunction "1_1") (pintype "passive"))
      (node (ref "C5") (pin "1") (pinfunction "1_1") (pintype "passive"))
      (node (ref "C6") (pin "1") (pinfunction "1_1") (pintype "passive"))
      (node (ref "C7") (pin "1") (pinfunction "1_1") (pintype "passive"))
      (node (ref "D1") (pin "2") (pinfunction "AN_2") (pintype "bidirectional"))
      (node (ref "D3") (pin "3") (pinfunction "K_3") (pintype "bidirectional"))
      (node (ref "D3") (pin "6") (pinfunction "K_6") (pintype "bidirectional"))
      (node (ref "D4") (pin "3") (pinfunction "K_3") (pintype "bidirectional"))
      (node (ref "D4") (pin "6") (pinfunction "K_6") (pintype "bidirectional"))
      (node (ref "D5") (pin "3") (pinfunction "K_3") (pintype "bidirectional"))
      (node (ref "D5") (pin "6") (pinfunction "K_6") (pintype "bidirectional"))
      (node (ref "D6") (pin "3") (pinfunction "K_3") (pintype "bidirectional"))
      (node (ref "D6") (pin "6") (pinfunction "K_6") (pintype "bidirectional"))
      (node (ref "D7") (pin "3") (pinfunction "K_3") (pintype "bidirectional"))
      (node (ref "D7") (pin "6") (pinfunction "K_6") (pintype "bidirectional"))
      (node (ref "IC1") (pin "1") (pinfunction "VCCIO_1") (pintype "bidirectional"))
      (node (ref "IC2") (pin "16") (pinfunction "VDD_16") (pintype "bidirectional"))
      (node (ref "IC2") (pin "2") (pinfunction "VDD_2") (pintype "bidirectional"))
      (node (ref "IC2") (pin "37") (pinfunction "VDD_37") (pintype "bidirectional"))
      (node (ref "IC2") (pin "46") (pinfunction "VDD_46") (pintype "bidirectional"))
      (node (ref "IC2") (pin "55") (pinfunction "VUSB_55") (pintype "bidirectional"))
      (node (ref "IC2") (pin "62") (pinfunction "VDD_62") (pintype "bidirectional"))
      (node (ref "IC2") (pin "86") (pinfunction "VDD_86") (pintype "bidirectional"))
      (node (ref "IC3") (pin "7") (pinfunction "SNS/ADJ_7") (pintype "bidirectional"))
      (node (ref "IC3") (pin "8") (pinfunction "VOUT_8") (pintype "bidirectional"))
      (node (ref "IC5") (pin "4") (pinfunction "IN-_4") (pintype "input"))
      (node (ref "J10") (pin "2") (pinfunction "2_2") (pintype "passive"))
      (node (ref "J10") (pin "4") (pinfunction "4_4") (pintype "passive"))
      (node (ref "J11") (pin "2") (pinfunction "2_2") (pintype "passive"))
      (node (ref "LD4") (pin "A") (pinfunction "A_A") (pintype "passive"))
      (node (ref "LD5") (pin "A") (pinfunction "A_A") (pintype "passive"))
      (node (ref "R10") (pin "2") (pinfunction "2_2") (pintype "passive"))
      (node (ref "R11") (pin "2") (pinfunction "2_2") (pintype "passive"))
      (node (ref "R12") (pin "2") (pinfunction "2_2") (pintype "passive"))
      (node (ref "R3") (pin "1") (pinfunction "1_1") (pintype "passive"))
      (node (ref "R4") (pin "2") (pinfunction "2_2") (pintype "passive"))
    )
    (net (code "144") (name "VCC5V0") (class "Default")
      (node (ref "C17") (pin "+") (pinfunction "+_+") (pintype "passive"))
      (node (ref "C20") (pin "1") (pinfunction "1_1") (pintype "passive"))
      (node (ref "C24") (pin "1") (pinfunction "1_1") (pintype "passive"))
      (node (ref "C25") (pin "1") (pinfunction "1_1") (pintype "passive"))
      (node (ref "IC1") (pin "19") (pinfunction "VCC_19") (pintype "bidirectional"))
      (node (ref "IC3") (pin "1") (pinfunction "VIN_1") (pintype "bidirectional"))
      (node (ref "IC3") (pin "2") (pinfunction "VIN_2") (pintype "bidirectional"))
      (node (ref "IC3") (pin "3") (pinfunction "SHDN_3") (pintype "bidirectional"))
      (node (ref "IC4") (pin "2") (pinfunction "OUT_2") (pintype "power_in"))
      (node (ref "IC4") (pin "TAB") (pinfunction "TAB_TAB") (pintype "power_in"))
      (node (ref "IC5") (pin "5") (pinfunction "VCC_5") (pintype "bidirectional"))
      (node (ref "J10") (pin "5") (pinfunction "5_5") (pintype "passive"))
      (node (ref "J6") (pin "1") (pinfunction "1_1") (pintype "passive"))
      (node (ref "J6") (pin "2") (pinfunction "2_2") (pintype "passive"))
      (node (ref "JP1") (pin "1") (pinfunction "1_1") (pintype "passive"))
      (node (ref "Q1") (pin "2") (pinfunction "S_2") (pintype "bidirectional"))
      (node (ref "R37") (pin "2") (pinfunction "2_2") (pintype "passive"))
      (node (ref "R44") (pin "2") (pinfunction "2_2") (pintype "passive"))
    )
    (net (code "145") (name "VCMP") (class "Default")
      (node (ref "D9") (pin "3") (pinfunction "COM_3") (pintype "bidirectional"))
      (node (ref "IC5") (pin "3") (pinfunction "IN+_3") (pintype "input"))
      (node (ref "R13") (pin "1") (pinfunction "1_1") (pintype "passive"))
      (node (ref "R14") (pin "2") (pinfunction "2_2") (pintype "passive"))
    )
    (net (code "146") (name "VIN") (class "Default")
      (node (ref "D9") (pin "2") (pinfunction "AN_2") (pintype "bidirectional"))
      (node (ref "J10") (pin "8") (pinfunction "8_8") (pintype "passive"))
      (node (ref "J2") (pin "1") (pinfunction "1_1") (pintype "passive"))
      (node (ref "JP1") (pin "2") (pinfunction "2_2") (pintype "passive"))
      (node (ref "R13") (pin "2") (pinfunction "2_2") (pintype "passive"))
    )
    (net (code "147") (name "VREF+{slash}PMA6{slash}RA10") (class "Default")
      (node (ref "J3") (pin "15") (pinfunction "15_15") (pintype "passive"))
      (node (ref "J8") (pin "10") (pinfunction "10_10") (pintype "passive"))
      (node (ref "R15") (pin "2") (pinfunction "2_2") (pintype "passive"))
    )
    (net (code "148") (name "VREF-{slash}PMA7{slash}RA9") (class "Default")
      (node (ref "J3") (pin "16") (pinfunction "16_16") (pintype "passive"))
      (node (ref "R33") (pin "2") (pinfunction "2_2") (pintype "passive"))
    )
    (net (code "149") (name "unconnected-(D8-D1-Pad1)") (class "Default")
      (node (ref "D8") (pin "1") (pinfunction "D1_1") (pintype "bidirectional"))
    )
    (net (code "150") (name "unconnected-(IC1-3V3OUT-Pad16)") (class "Default")
      (node (ref "IC1") (pin "16") (pinfunction "3V3OUT_16") (pintype "bidirectional"))
    )
    (net (code "151") (name "unconnected-(IC1-CBUS2-Pad10)") (class "Default")
      (node (ref "IC1") (pin "10") (pinfunction "CBUS2_10") (pintype "bidirectional"))
    )
    (net (code "152") (name "unconnected-(IC1-CBUS3-Pad11)") (class "Default")
      (node (ref "IC1") (pin "11") (pinfunction "CBUS3_11") (pintype "bidirectional"))
    )
    (net (code "153") (name "unconnected-(IC1-CBUS4-Pad9)") (class "Default")
      (node (ref "IC1") (pin "9") (pinfunction "CBUS4_9") (pintype "bidirectional"))
    )
    (net (code "154") (name "unconnected-(IC1-OSCI-Pad27)") (class "Default")
      (node (ref "IC1") (pin "27") (pinfunction "OSCI_27") (pintype "bidirectional"))
    )
    (net (code "155") (name "unconnected-(IC1-OSCO-Pad28)") (class "Default")
      (node (ref "IC1") (pin "28") (pinfunction "OSCO_28") (pintype "bidirectional"))
    )
    (net (code "156") (name "unconnected-(IC3-PWRGD-Pad5)") (class "Default")
      (node (ref "IC3") (pin "5") (pinfunction "PWRGD_5") (pintype "bidirectional"))
    )
    (net (code "157") (name "unconnected-(J1-ID-Pad4)") (class "Default")
      (node (ref "J1") (pin "4") (pinfunction "ID_4") (pintype "bidirectional"))
    )
    (net (code "158") (name "unconnected-(J10-Pad1)") (class "Default")
      (node (ref "J10") (pin "1") (pinfunction "1_1") (pintype "passive"))
    )
    (net (code "159") (name "unconnected-(J11-Pad6)") (class "Default")
      (node (ref "J11") (pin "6") (pinfunction "6_6") (pintype "passive"))
    )
    (net (code "160") (name "unconnected-(J13-Pad2)") (class "Default")
      (node (ref "J13") (pin "2") (pinfunction "2_2") (pintype "passive"))
    )
  )
)
